# tottag.net
KiCad netlist of a schematic drawn in EAGLE
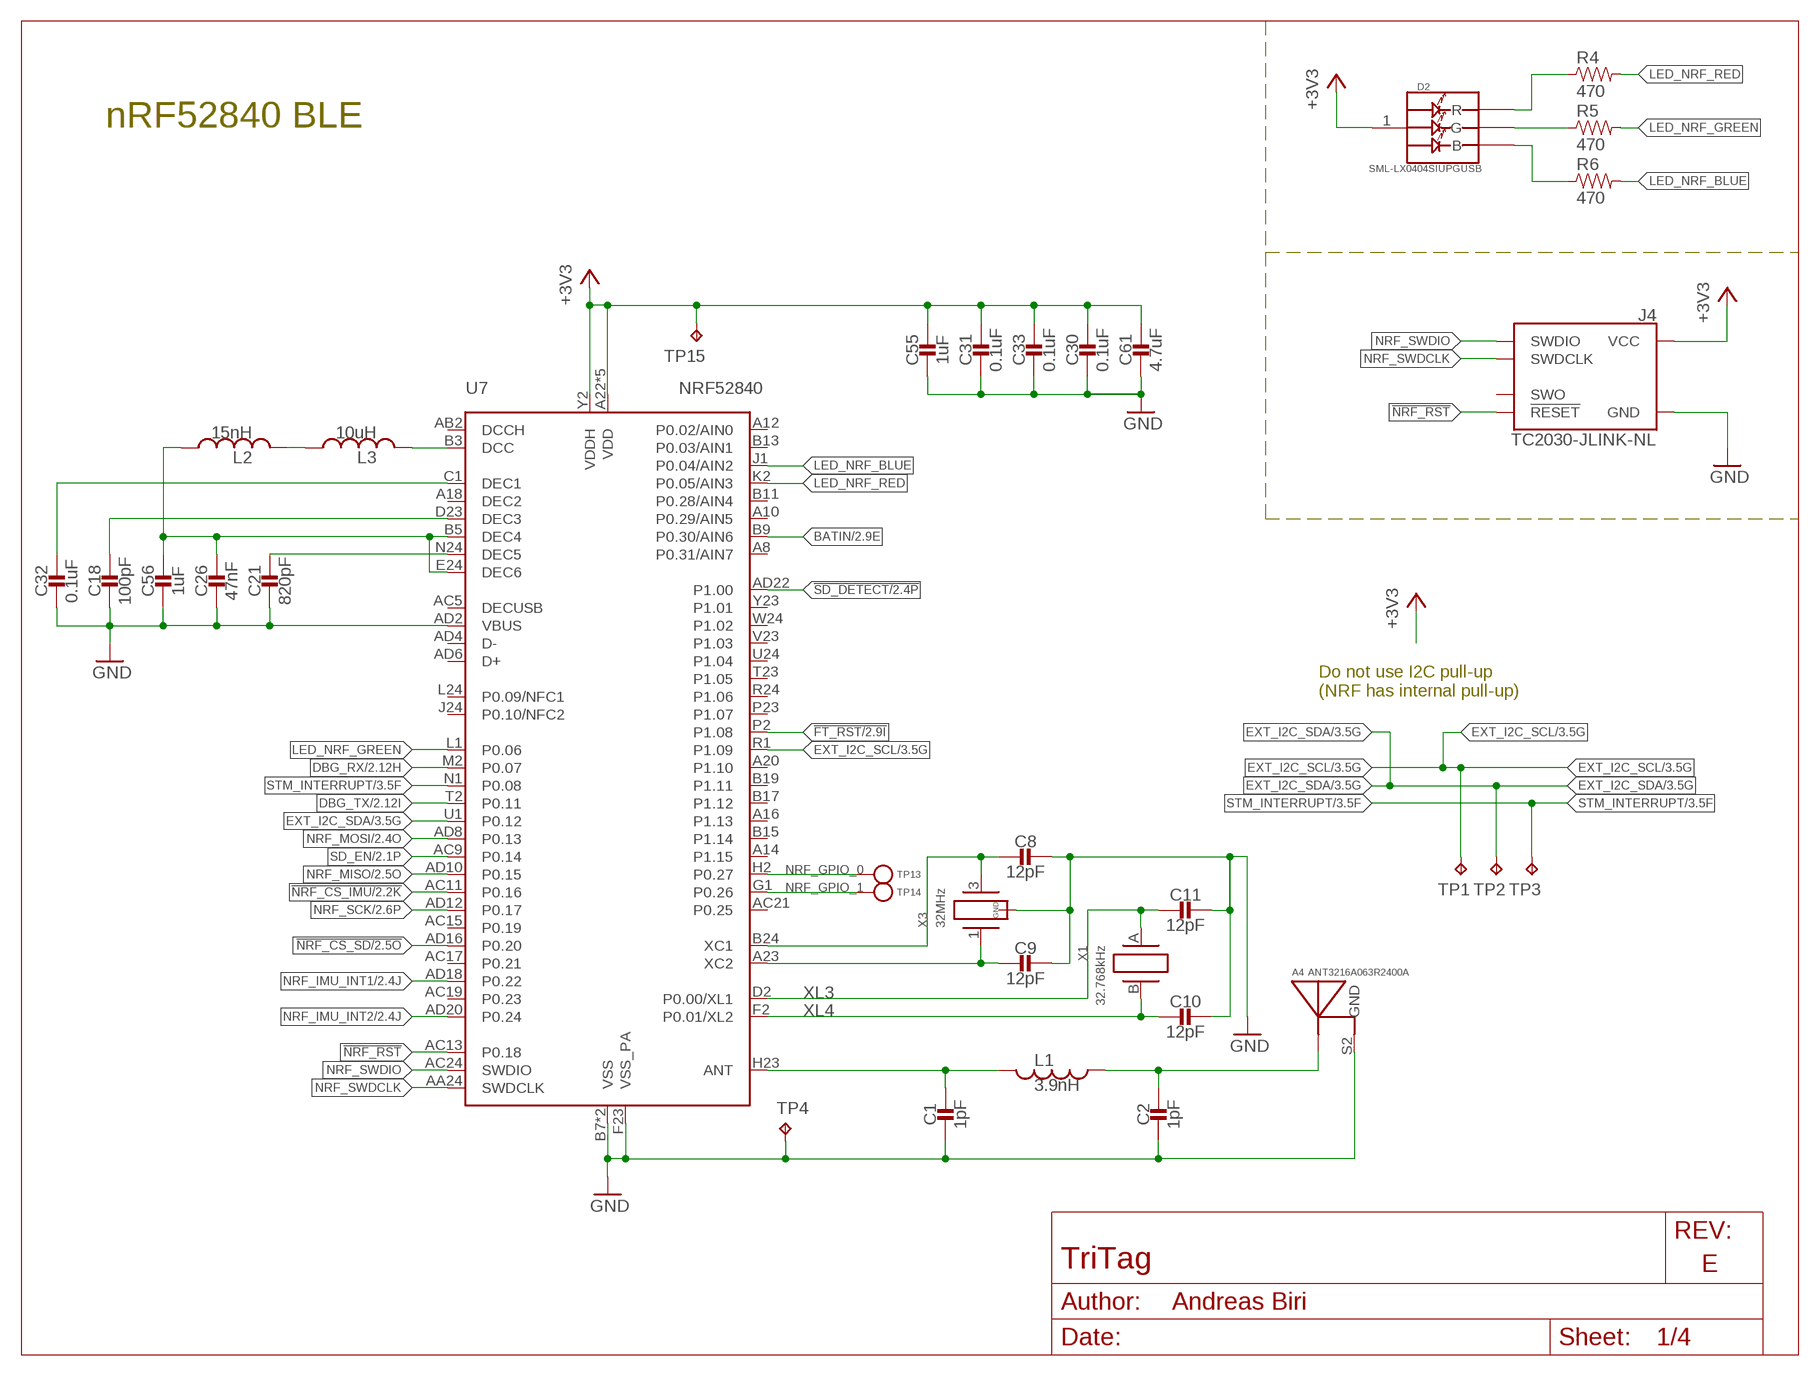
[diagram p0: schematic, sheet 1]
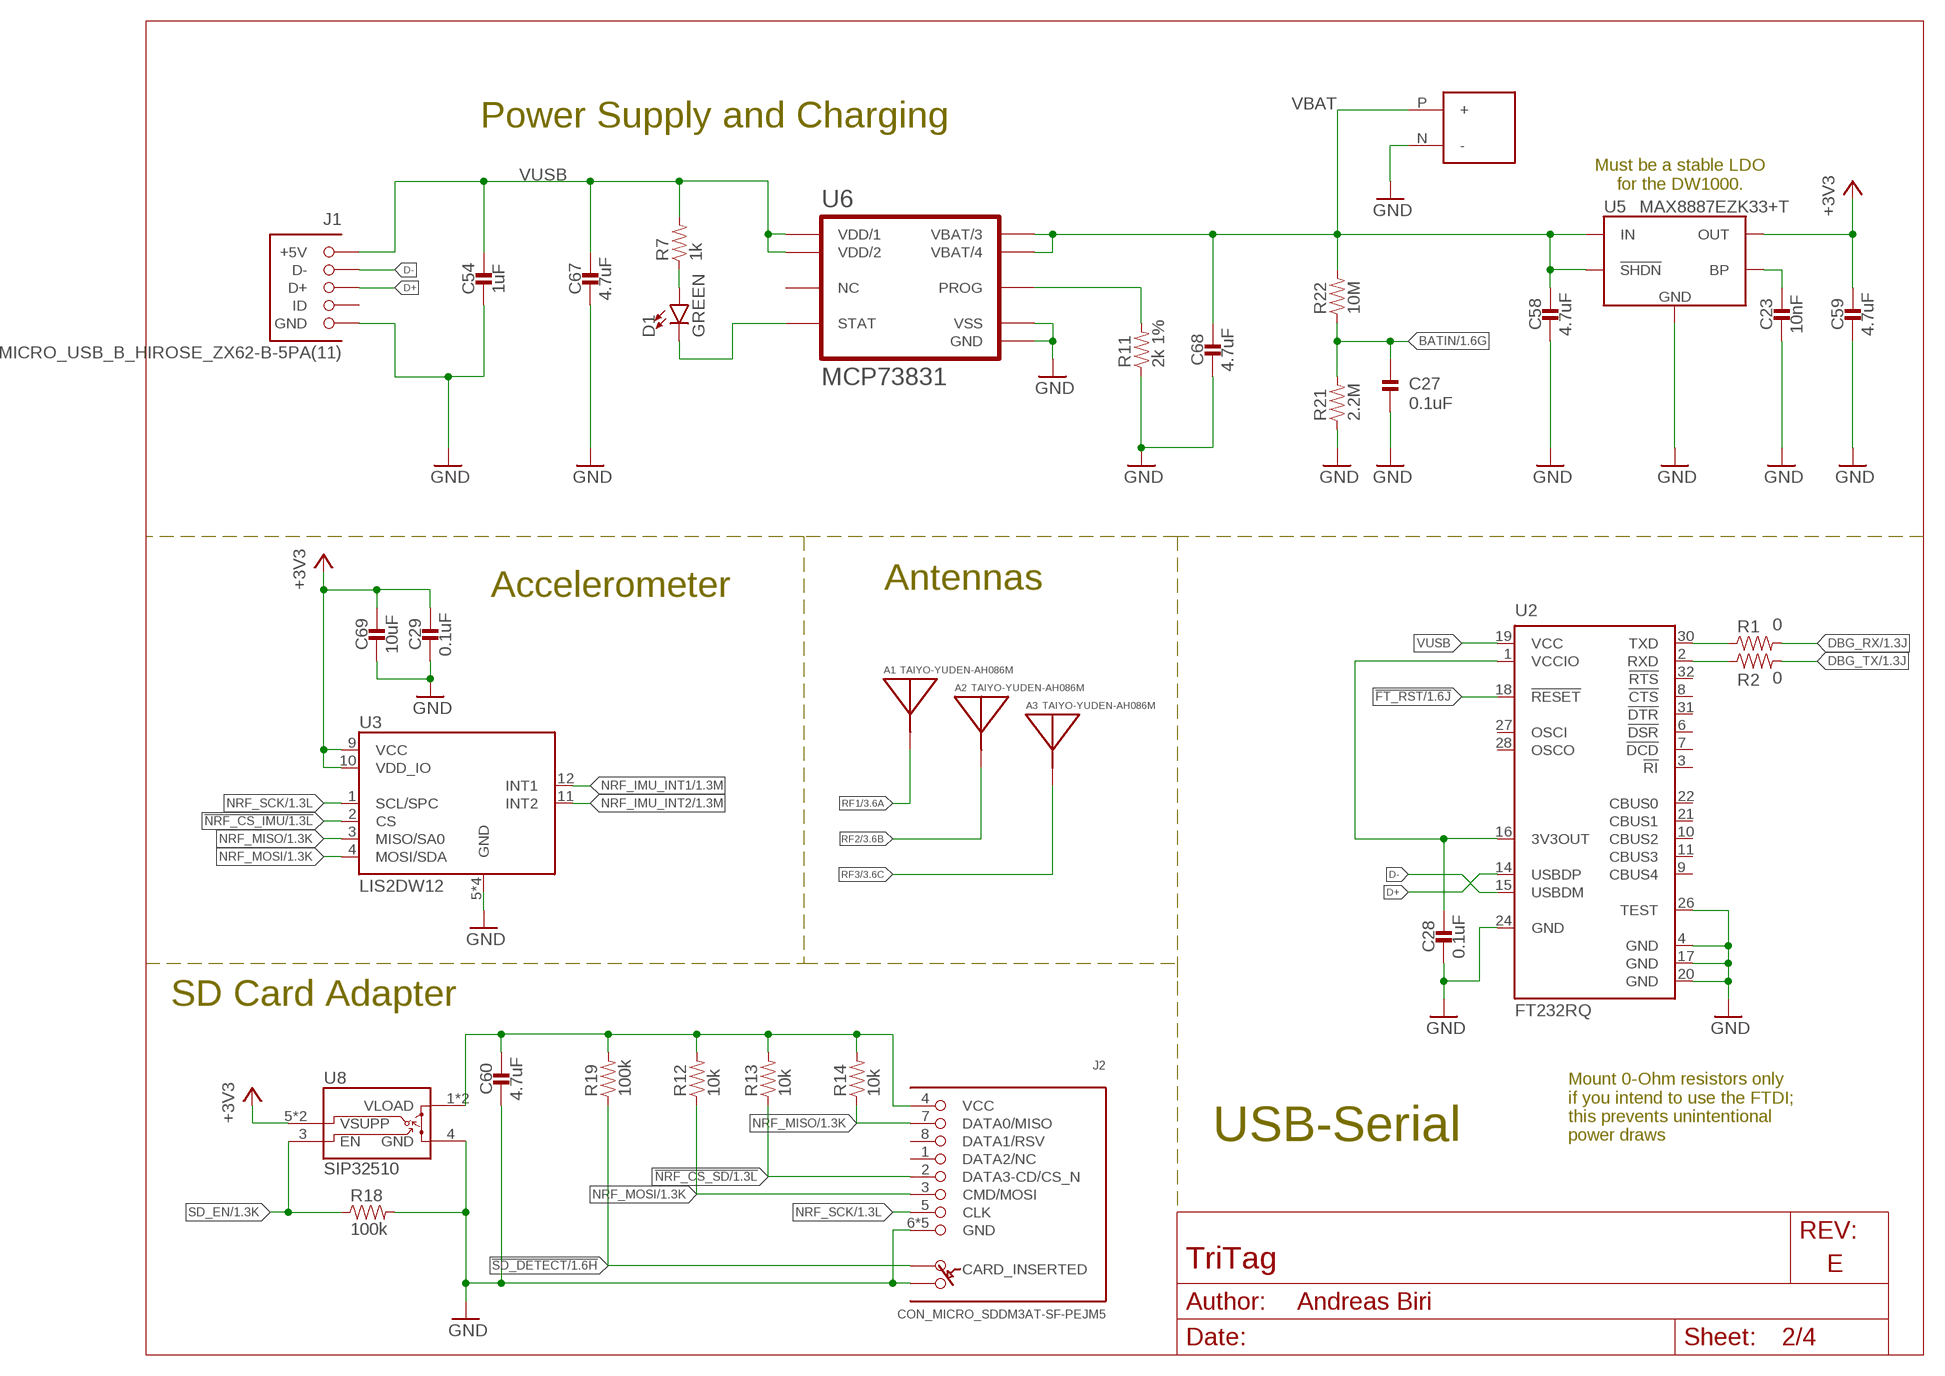
[diagram p1: schematic, sheet 2]
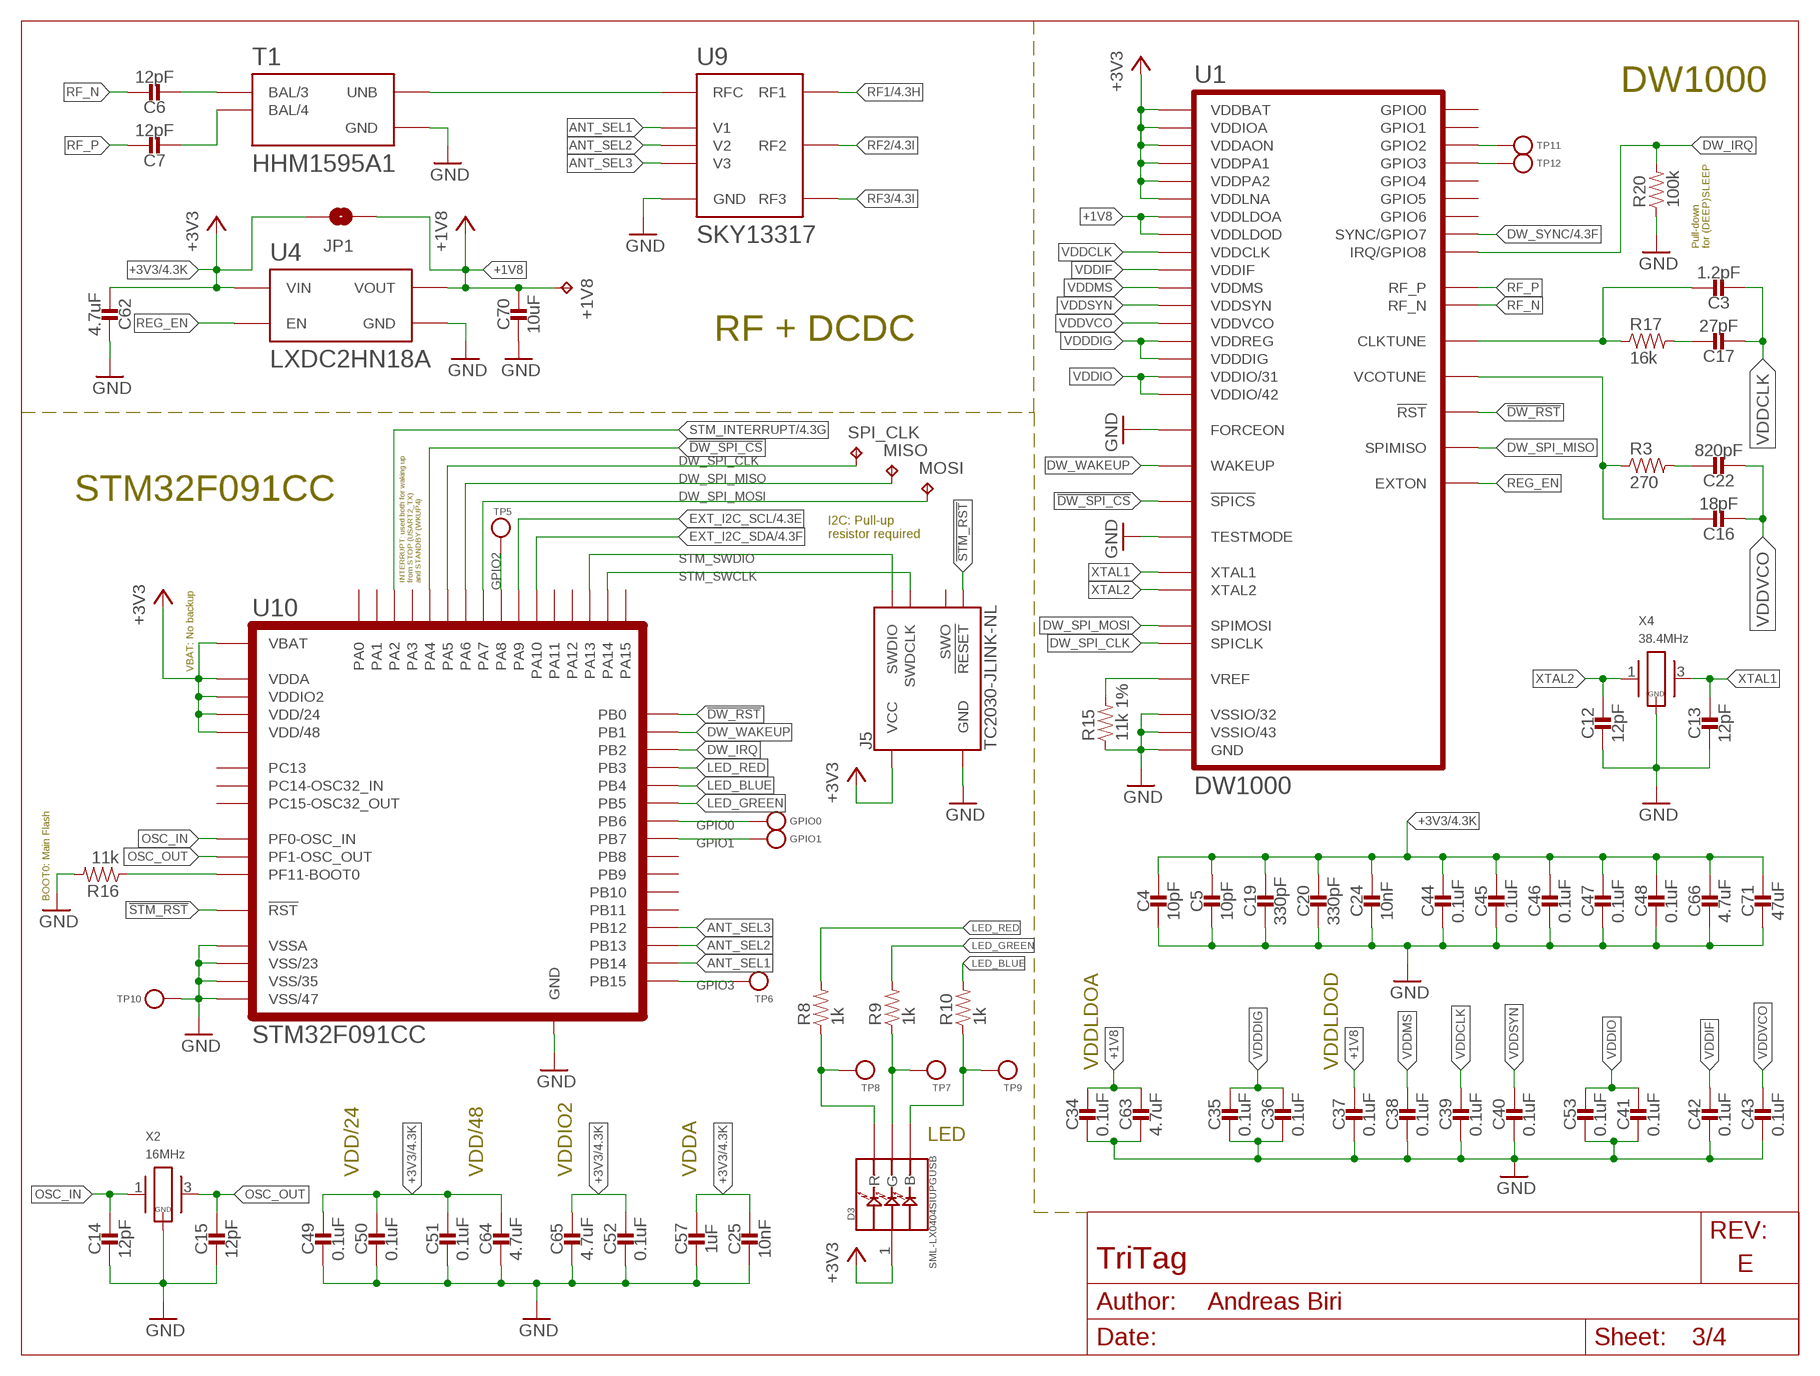
[diagram p2: schematic, sheet 3]
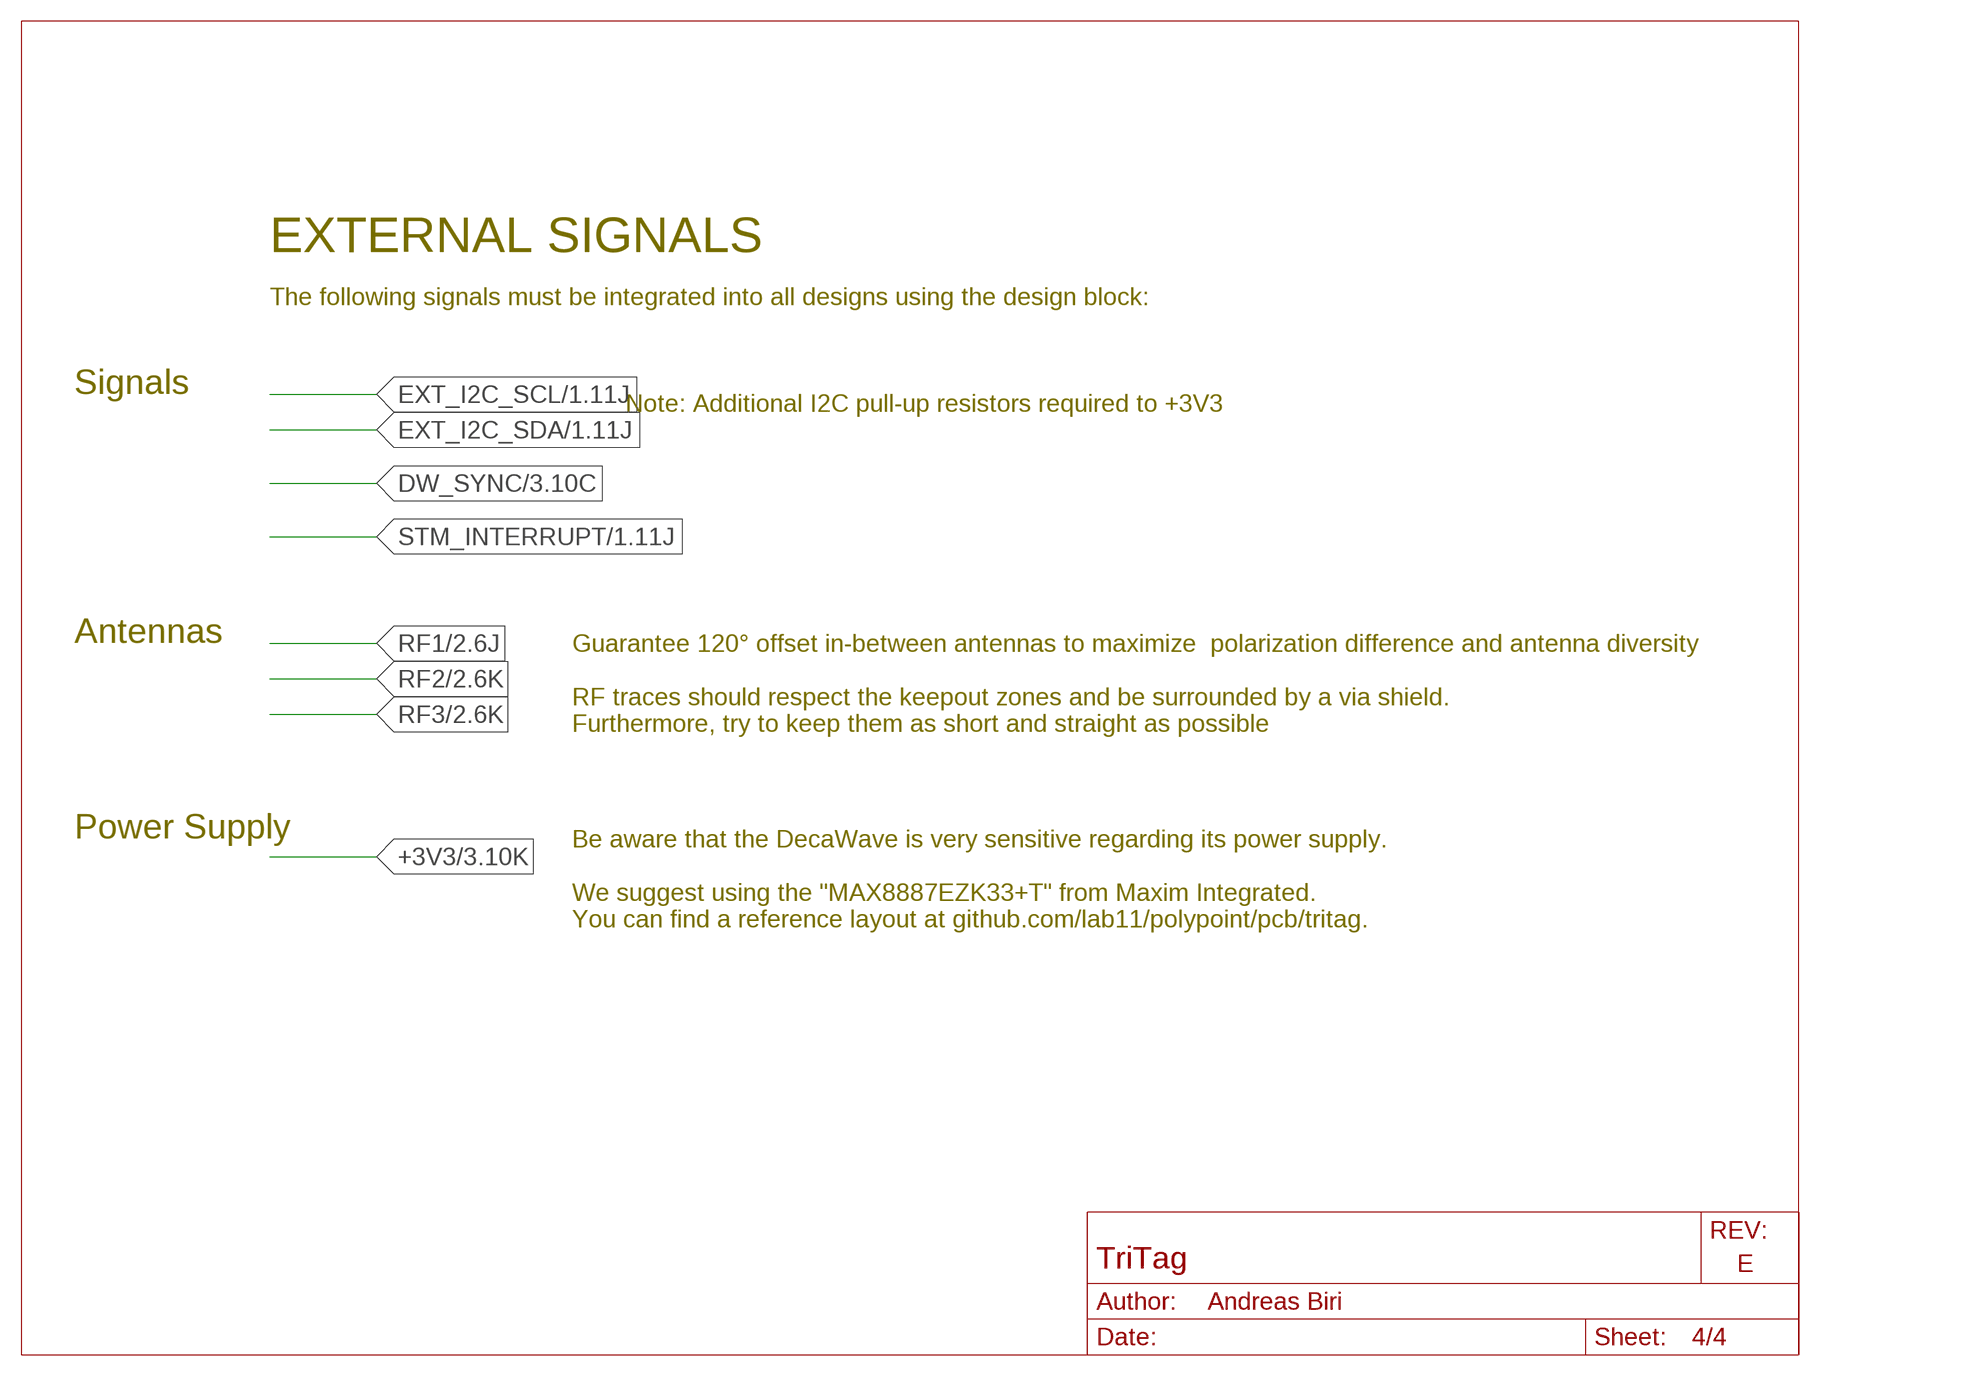
[diagram p3: schematic, sheet 4]

(export (version "E")
  (design (tool "Eeschema 10.0.6"))
  (components
    (comp (ref "A1")
      (value "TAIYO-YUDEN-AH086M")
      (footprint "eagle-import:TAIYO-YUDEN-AH086M")
      (libsource (lib "eagle-import") (part "TAIYO-YUDEN-AH086M"))
    )
    (comp (ref "A2")
      (value "TAIYO-YUDEN-AH086M")
      (footprint "eagle-import:TAIYO-YUDEN-AH086M")
      (libsource (lib "eagle-import") (part "TAIYO-YUDEN-AH086M"))
    )
    (comp (ref "A3")
      (value "TAIYO-YUDEN-AH086M")
      (footprint "eagle-import:TAIYO-YUDEN-AH086M")
      (libsource (lib "eagle-import") (part "TAIYO-YUDEN-AH086M"))
    )
    (comp (ref "C23")
      (value "10nF")
      (footprint "eagle-import:0402_CAP")
      (libsource (lib "eagle-import") (part "CAPACITOR0402_CAP"))
    )
    (comp (ref "C27")
      (value "0.1uF")
      (footprint "eagle-import:0402_CAP")
      (libsource (lib "eagle-import") (part "CAPACITOR0402_CAP"))
    )
    (comp (ref "C28")
      (value "0.1uF")
      (footprint "eagle-import:0402_CAP")
      (fields (field (name "MPN") "GRM155R71C104KA88J "))
      (libsource (lib "eagle-import") (part "CAPACITOR0402_CAP"))
    )
    (comp (ref "C29")
      (value "0.1uF")
      (footprint "eagle-import:0402_CAP")
      (fields (field (name "MPN") "GRM155R71C104KA88J "))
      (libsource (lib "eagle-import") (part "CAPACITOR0402_CAP"))
    )
    (comp (ref "C54")
      (value "1uF")
      (footprint "eagle-import:0402_CAP")
      (libsource (lib "eagle-import") (part "CAPACITOR0402_CAP"))
    )
    (comp (ref "C58")
      (value "4.7uF")
      (footprint "eagle-import:0402_CAP")
      (libsource (lib "eagle-import") (part "CAPACITOR0402_CAP"))
    )
    (comp (ref "C59")
      (value "4.7uF")
      (footprint "eagle-import:0402_CAP")
      (libsource (lib "eagle-import") (part "CAPACITOR0402_CAP"))
    )
    (comp (ref "C60")
      (value "4.7uF")
      (footprint "eagle-import:0402_CAP")
      (description "CAP CER 4.7UF 6.3V X5R 0402")
      (fields (field (name "MANUFACTURER") "TDK") (field (name "MPN") "C1005X5R0J475K050BC"))
      (libsource (lib "eagle-import") (part "CAPACITOR0402_CAP"))
    )
    (comp (ref "C67")
      (value "4.7uF")
      (footprint "eagle-import:0402_CAP")
      (libsource (lib "eagle-import") (part "CAPACITOR0402_CAP"))
    )
    (comp (ref "C68")
      (value "4.7uF")
      (footprint "eagle-import:0402_CAP")
      (libsource (lib "eagle-import") (part "CAPACITOR0402_CAP"))
    )
    (comp (ref "C69")
      (value "10uF")
      (footprint "eagle-import:0603_CAP")
      (fields (field (name "MPN") "GRM188R60J106ME47D "))
      (libsource (lib "eagle-import") (part "CAPACITOR0603_CAP"))
    )
    (comp (ref "D1")
      (value "GREEN")
      (footprint "eagle-import:LED-0603")
      (libsource (lib "eagle-import") (part "LED0603"))
    )
    (comp (ref "J1")
      (value "MICRO_USB_B_HIROSE_ZX62-B-5PA(11)")
      (footprint "eagle-import:USB_MICRO_B-HIROSE-ZX62-B-5PA(11)")
      (libsource (lib "eagle-import") (part "MICRO_USB_B_HIROSE_ZX62-B-5PA(11)"))
    )
    (comp (ref "J2")
      (value "CON_MICRO_SDDM3AT-SF-PEJM5")
      (footprint "eagle-import:DM3AT-SF-PEJM5")
      (libsource (lib "eagle-import") (part "CON_MICRO_SDDM3AT-SF-PEJM5"))
    )
    (comp (ref "J3")
      (value "BAT_HOLE")
      (footprint "eagle-import:BATTERY_HOLE")
      (libsource (lib "eagle-import") (part "BAT_HOLE"))
    )
    (comp (ref "R1")
      (value "0")
      (footprint "eagle-import:0402_RES")
      (libsource (lib "eagle-import") (part "RESISTOR0402_RES"))
    )
    (comp (ref "R2")
      (value "0")
      (footprint "eagle-import:0402_RES")
      (libsource (lib "eagle-import") (part "RESISTOR0402_RES"))
    )
    (comp (ref "R7")
      (value "1k")
      (footprint "eagle-import:0402_RES")
      (libsource (lib "eagle-import") (part "RESISTOR0402_RES"))
    )
    (comp (ref "R11")
      (value "2k 1%")
      (footprint "eagle-import:0402_RES")
      (libsource (lib "eagle-import") (part "RESISTOR0402_RES"))
    )
    (comp (ref "R12")
      (value "10k")
      (footprint "eagle-import:0402_RES")
      (libsource (lib "eagle-import") (part "RESISTOR0402_RES"))
    )
    (comp (ref "R13")
      (value "10k")
      (footprint "eagle-import:0402_RES")
      (libsource (lib "eagle-import") (part "RESISTOR0402_RES"))
    )
    (comp (ref "R14")
      (value "10k")
      (footprint "eagle-import:0402_RES")
      (libsource (lib "eagle-import") (part "RESISTOR0402_RES"))
    )
    (comp (ref "R18")
      (value "100k")
      (footprint "eagle-import:0402_RES")
      (libsource (lib "eagle-import") (part "RESISTOR0402_RES"))
    )
    (comp (ref "R19")
      (value "100k")
      (footprint "eagle-import:0402_RES")
      (libsource (lib "eagle-import") (part "RESISTOR0402_RES"))
    )
    (comp (ref "R21")
      (value "2.2M")
      (footprint "eagle-import:0402_RES")
      (libsource (lib "eagle-import") (part "RESISTOR0402_RES"))
    )
    (comp (ref "R22")
      (value "10M")
      (footprint "eagle-import:0402_RES")
      (libsource (lib "eagle-import") (part "RESISTOR0402_RES"))
    )
    (comp (ref "U2")
      (value "FT232RQ")
      (footprint "eagle-import:QFN32")
      (libsource (lib "eagle-import") (part "FT232RQ"))
    )
    (comp (ref "U3")
      (value "LIS2DW12")
      (footprint "eagle-import:LGA-12")
      (fields (field (name "MANUFACTURER") "STMicroelectronics") (field (name "MPN") "LIS2DW12TR"))
      (libsource (lib "eagle-import") (part "LIS2DW12"))
    )
    (comp (ref "U5")
      (value "MAX8887EZK33+T")
      (footprint "eagle-import:SOT-23-5")
      (libsource (lib "eagle-import") (part "MAX8887EZK33+T"))
    )
    (comp (ref "U6")
      (value "MCP73831")
      (footprint "eagle-import:DFN-8-MCP")
      (fields (field (name "MANUFACTURER") "Microchip Technology") (field (name "MPN") "MCP73831T-2ACI/MC"))
      (libsource (lib "eagle-import") (part "MCP73831"))
    )
    (comp (ref "U8")
      (value "SIP32510")
      (footprint "eagle-import:TSOT23-6")
      (fields (field (name "MANUFACTURER") "Vishay") (field (name "MPN") "SIP32510DT-T1-GE3"))
      (libsource (lib "eagle-import") (part "SIP32510"))
    )
    (comp (ref "+1V8")
      (value "TPTP06SQ")
      (footprint "eagle-import:TP06SQ")
      (libsource (lib "eagle-import") (part "TPTP06SQ"))
    )
    (comp (ref "C3")
      (value "1.2pF")
      (footprint "eagle-import:0402_CAP")
      (libsource (lib "eagle-import") (part "CAPACITOR0402_CAP"))
    )
    (comp (ref "C4")
      (value "10pF")
      (footprint "eagle-import:0402_CAP")
      (libsource (lib "eagle-import") (part "CAPACITOR0402_CAP"))
    )
    (comp (ref "C5")
      (value "10pF")
      (footprint "eagle-import:0402_CAP")
      (libsource (lib "eagle-import") (part "CAPACITOR0402_CAP"))
    )
    (comp (ref "C6")
      (value "12pF")
      (footprint "eagle-import:0201_CAP")
      (libsource (lib "eagle-import") (part "CAPACITOR0201_CAP"))
    )
    (comp (ref "C7")
      (value "12pF")
      (footprint "eagle-import:0201_CAP")
      (libsource (lib "eagle-import") (part "CAPACITOR0201_CAP"))
    )
    (comp (ref "C12")
      (value "12pF")
      (footprint "eagle-import:0402_CAP")
      (libsource (lib "eagle-import") (part "CAPACITOR0402_CAP"))
    )
    (comp (ref "C13")
      (value "12pF")
      (footprint "eagle-import:0402_CAP")
      (libsource (lib "eagle-import") (part "CAPACITOR0402_CAP"))
    )
    (comp (ref "C14")
      (value "12pF")
      (footprint "eagle-import:0402_CAP")
      (libsource (lib "eagle-import") (part "CAPACITOR0402_CAP"))
    )
    (comp (ref "C15")
      (value "12pF")
      (footprint "eagle-import:0402_CAP")
      (libsource (lib "eagle-import") (part "CAPACITOR0402_CAP"))
    )
    (comp (ref "C16")
      (value "18pF")
      (footprint "eagle-import:0402_CAP")
      (libsource (lib "eagle-import") (part "CAPACITOR0402_CAP"))
    )
    (comp (ref "C17")
      (value "27pF")
      (footprint "eagle-import:0402_CAP")
      (libsource (lib "eagle-import") (part "CAPACITOR0402_CAP"))
    )
    (comp (ref "C19")
      (value "330pF")
      (footprint "eagle-import:0402_CAP")
      (libsource (lib "eagle-import") (part "CAPACITOR0402_CAP"))
    )
    (comp (ref "C20")
      (value "330pF")
      (footprint "eagle-import:0402_CAP")
      (libsource (lib "eagle-import") (part "CAPACITOR0402_CAP"))
    )
    (comp (ref "C22")
      (value "820pF")
      (footprint "eagle-import:0402_CAP")
      (libsource (lib "eagle-import") (part "CAPACITOR0402_CAP"))
    )
    (comp (ref "C24")
      (value "10nF")
      (footprint "eagle-import:0402_CAP")
      (libsource (lib "eagle-import") (part "CAPACITOR0402_CAP"))
    )
    (comp (ref "C25")
      (value "10nF")
      (footprint "eagle-import:0402_CAP")
      (libsource (lib "eagle-import") (part "CAPACITOR0402_CAP"))
    )
    (comp (ref "C34")
      (value "0.1uF")
      (footprint "eagle-import:0402_CAP")
      (libsource (lib "eagle-import") (part "CAPACITOR0402_CAP"))
    )
    (comp (ref "C35")
      (value "0.1uF")
      (footprint "eagle-import:0402_CAP")
      (libsource (lib "eagle-import") (part "CAPACITOR0402_CAP"))
    )
    (comp (ref "C36")
      (value "0.1uF")
      (footprint "eagle-import:0402_CAP")
      (libsource (lib "eagle-import") (part "CAPACITOR0402_CAP"))
    )
    (comp (ref "C37")
      (value "0.1uF")
      (footprint "eagle-import:0402_CAP")
      (libsource (lib "eagle-import") (part "CAPACITOR0402_CAP"))
    )
    (comp (ref "C38")
      (value "0.1uF")
      (footprint "eagle-import:0402_CAP")
      (libsource (lib "eagle-import") (part "CAPACITOR0402_CAP"))
    )
    (comp (ref "C39")
      (value "0.1uF")
      (footprint "eagle-import:0402_CAP")
      (libsource (lib "eagle-import") (part "CAPACITOR0402_CAP"))
    )
    (comp (ref "C40")
      (value "0.1uF")
      (footprint "eagle-import:0402_CAP")
      (libsource (lib "eagle-import") (part "CAPACITOR0402_CAP"))
    )
    (comp (ref "C41")
      (value "0.1uF")
      (footprint "eagle-import:0402_CAP")
      (libsource (lib "eagle-import") (part "CAPACITOR0402_CAP"))
    )
    (comp (ref "C42")
      (value "0.1uF")
      (footprint "eagle-import:0402_CAP")
      (libsource (lib "eagle-import") (part "CAPACITOR0402_CAP"))
    )
    (comp (ref "C43")
      (value "0.1uF")
      (footprint "eagle-import:0402_CAP")
      (libsource (lib "eagle-import") (part "CAPACITOR0402_CAP"))
    )
    (comp (ref "C44")
      (value "0.1uF")
      (footprint "eagle-import:0402_CAP")
      (libsource (lib "eagle-import") (part "CAPACITOR0402_CAP"))
    )
    (comp (ref "C45")
      (value "0.1uF")
      (footprint "eagle-import:0402_CAP")
      (libsource (lib "eagle-import") (part "CAPACITOR0402_CAP"))
    )
    (comp (ref "C46")
      (value "0.1uF")
      (footprint "eagle-import:0402_CAP")
      (libsource (lib "eagle-import") (part "CAPACITOR0402_CAP"))
    )
    (comp (ref "C47")
      (value "0.1uF")
      (footprint "eagle-import:0402_CAP")
      (libsource (lib "eagle-import") (part "CAPACITOR0402_CAP"))
    )
    (comp (ref "C48")
      (value "0.1uF")
      (footprint "eagle-import:0402_CAP")
      (libsource (lib "eagle-import") (part "CAPACITOR0402_CAP"))
    )
    (comp (ref "C49")
      (value "0.1uF")
      (footprint "eagle-import:0402_CAP")
      (libsource (lib "eagle-import") (part "CAPACITOR0402_CAP"))
    )
    (comp (ref "C50")
      (value "0.1uF")
      (footprint "eagle-import:0402_CAP")
      (libsource (lib "eagle-import") (part "CAPACITOR0402_CAP"))
    )
    (comp (ref "C51")
      (value "0.1uF")
      (footprint "eagle-import:0402_CAP")
      (libsource (lib "eagle-import") (part "CAPACITOR0402_CAP"))
    )
    (comp (ref "C52")
      (value "0.1uF")
      (footprint "eagle-import:0402_CAP")
      (libsource (lib "eagle-import") (part "CAPACITOR0402_CAP"))
    )
    (comp (ref "C53")
      (value "0.1uF")
      (footprint "eagle-import:0402_CAP")
      (libsource (lib "eagle-import") (part "CAPACITOR0402_CAP"))
    )
    (comp (ref "C57")
      (value "1uF")
      (footprint "eagle-import:0402_CAP")
      (libsource (lib "eagle-import") (part "CAPACITOR0402_CAP"))
    )
    (comp (ref "C62")
      (value "4.7uF")
      (footprint "eagle-import:0402_CAP")
      (libsource (lib "eagle-import") (part "CAPACITOR0402_CAP"))
    )
    (comp (ref "C63")
      (value "4.7uF")
      (footprint "eagle-import:0402_CAP")
      (libsource (lib "eagle-import") (part "CAPACITOR0402_CAP"))
    )
    (comp (ref "C64")
      (value "4.7uF")
      (footprint "eagle-import:0402_CAP")
      (libsource (lib "eagle-import") (part "CAPACITOR0402_CAP"))
    )
    (comp (ref "C65")
      (value "4.7uF")
      (footprint "eagle-import:0402_CAP")
      (libsource (lib "eagle-import") (part "CAPACITOR0402_CAP"))
    )
    (comp (ref "C66")
      (value "4.7uF")
      (footprint "eagle-import:0402_CAP")
      (libsource (lib "eagle-import") (part "CAPACITOR0402_CAP"))
    )
    (comp (ref "C70")
      (value "10uF")
      (footprint "eagle-import:0603_CAP")
      (libsource (lib "eagle-import") (part "CAPACITOR0603_CAP"))
    )
    (comp (ref "C71")
      (value "47uF")
      (footprint "eagle-import:0603_CAP")
      (libsource (lib "eagle-import") (part "CAPACITOR0603_CAP"))
    )
    (comp (ref "D3")
      (value "SML-LX0404SIUPGUSB")
      (footprint "eagle-import:1MM_SQ_4PAD")
      (fields (field (name "MANUFACTURER") "Lumex Opto"))
      (libsource (lib "eagle-import") (part "SML-LX0404SIUPGUSB"))
    )
    (comp (ref "GPIO0")
      (value "TEST-POINT")
      (footprint "eagle-import:PAD.03X.03")
      (libsource (lib "eagle-import") (part "TEST-POINT"))
    )
    (comp (ref "GPIO1")
      (value "TEST-POINT")
      (footprint "eagle-import:PAD.03X.03")
      (libsource (lib "eagle-import") (part "TEST-POINT"))
    )
    (comp (ref "J5")
      (value "TC2030-JLINK-NL")
      (footprint "eagle-import:TC2030-IDC-NL")
      (libsource (lib "eagle-import") (part "TC2030-JLINK-NL"))
    )
    (comp (ref "JP1")
      (value "JUMPER-SMT_2_NO_NO-SILK")
      (footprint "eagle-import:SMT-JUMPER_2_NO_NO-SILK")
      (libsource (lib "eagle-import") (part "JUMPER-SMT_2_NO_NO-SILK"))
    )
    (comp (ref "MISO")
      (value "TPTP06SQ")
      (footprint "eagle-import:TP06SQ")
      (libsource (lib "eagle-import") (part "TPTP06SQ"))
    )
    (comp (ref "MOSI")
      (value "TPTP06SQ")
      (footprint "eagle-import:TP06SQ")
      (libsource (lib "eagle-import") (part "TPTP06SQ"))
    )
    (comp (ref "R3")
      (value "270")
      (footprint "eagle-import:0402_RES")
      (libsource (lib "eagle-import") (part "RESISTOR0402_RES"))
    )
    (comp (ref "R8")
      (value "1k")
      (footprint "eagle-import:0402_RES")
      (libsource (lib "eagle-import") (part "RESISTOR0402_RES"))
    )
    (comp (ref "R9")
      (value "1k")
      (footprint "eagle-import:0402_RES")
      (libsource (lib "eagle-import") (part "RESISTOR0402_RES"))
    )
    (comp (ref "R10")
      (value "1k")
      (footprint "eagle-import:0402_RES")
      (libsource (lib "eagle-import") (part "RESISTOR0402_RES"))
    )
    (comp (ref "R15")
      (value "11k 1%")
      (footprint "eagle-import:0402_RES")
      (libsource (lib "eagle-import") (part "RESISTOR0402_RES"))
    )
    (comp (ref "R16")
      (value "11k")
      (footprint "eagle-import:0402_RES")
      (libsource (lib "eagle-import") (part "RESISTOR0402_RES"))
    )
    (comp (ref "R17")
      (value "16k")
      (footprint "eagle-import:0402_RES")
      (libsource (lib "eagle-import") (part "RESISTOR0402_RES"))
    )
    (comp (ref "R20")
      (value "100k")
      (footprint "eagle-import:0402_RES")
      (libsource (lib "eagle-import") (part "RESISTOR0402_RES"))
    )
    (comp (ref "SPI_CLK")
      (value "TPTP06SQ")
      (footprint "eagle-import:TP06SQ")
      (libsource (lib "eagle-import") (part "TPTP06SQ"))
    )
    (comp (ref "T1")
      (value "HHM1595A1")
      (footprint "eagle-import:EIA-0805")
      (fields (field (name "MANUFACTURER") "TDK Corporation"))
      (libsource (lib "eagle-import") (part "HHM1595A1"))
    )
    (comp (ref "TP5")
      (value "TEST-POINT")
      (footprint "eagle-import:PAD.03X.03")
      (libsource (lib "eagle-import") (part "TEST-POINT"))
    )
    (comp (ref "TP6")
      (value "TEST-POINT")
      (footprint "eagle-import:PAD.03X.03")
      (libsource (lib "eagle-import") (part "TEST-POINT"))
    )
    (comp (ref "TP7")
      (value "TEST-POINT")
      (footprint "eagle-import:PAD.03X.03")
      (libsource (lib "eagle-import") (part "TEST-POINT"))
    )
    (comp (ref "TP8")
      (value "TEST-POINT")
      (footprint "eagle-import:PAD.03X.03")
      (libsource (lib "eagle-import") (part "TEST-POINT"))
    )
    (comp (ref "TP9")
      (value "TEST-POINT")
      (footprint "eagle-import:PAD.03X.03")
      (libsource (lib "eagle-import") (part "TEST-POINT"))
    )
    (comp (ref "TP10")
      (value "TEST-POINT")
      (footprint "eagle-import:PAD.03X.03")
      (libsource (lib "eagle-import") (part "TEST-POINT"))
    )
    (comp (ref "TP11")
      (value "TEST-POINT")
      (footprint "eagle-import:PAD.03X.03")
      (libsource (lib "eagle-import") (part "TEST-POINT"))
    )
    (comp (ref "TP12")
      (value "TEST-POINT")
      (footprint "eagle-import:PAD.03X.03")
      (libsource (lib "eagle-import") (part "TEST-POINT"))
    )
    (comp (ref "U1")
      (value "DW1000")
      (footprint "eagle-import:QFN-48-DW1000")
      (fields (field (name "MANUFACTURER") "Decawave Limited") (field (name "MPN") "DW1000-I-TR13"))
      (libsource (lib "eagle-import") (part "DW1000"))
    )
    (comp (ref "U4")
      (value "LXDC2HN18A")
      (footprint "eagle-import:LXDC2HN")
      (fields
        (field (name "MANUFACTURER") "Murata Electronics North America")
        (field (name "MPN") "LXDC2HN18A-097")
      )
      (libsource (lib "eagle-import") (part "LXDC2HN18A"))
    )
    (comp (ref "U9")
      (value "SKY13317")
      (footprint "eagle-import:MLPQ-UT-8")
      (fields (field (name "MANUFACTURER") "Skyworks Solutions Inc.") (field (name "MPN") "SKY13317-373LF"))
      (libsource (lib "eagle-import") (part "SKY13317"))
    )
    (comp (ref "U10")
      (value "STM32F091CC")
      (footprint "eagle-import:UFQFPN-48")
      (fields (field (name "MANUFACTURER") "STMicroelectronics") (field (name "MPN") "STM32F091CCU6"))
      (libsource (lib "eagle-import") (part "STM32F091CC"))
    )
    (comp (ref "X2")
      (value "16MHz")
      (footprint "eagle-import:FA-20H")
      (description "16MHz ±10ppm Crystal 8pF 80 Ohms 4-SMD, No Lead")
      (fields (field (name "MANUFACTURER") "EPSON"))
      (libsource (lib "eagle-import") (part "FA-20H"))
    )
    (comp (ref "X4")
      (value "38.4MHz")
      (footprint "eagle-import:FA-20H")
      (description "38.4MHz ±10ppm Crystal 8.5pF 40 Ohms 4-SMD, No Lead")
      (fields (field (name "MANUFACTURER") "EPSON"))
      (libsource (lib "eagle-import") (part "FA-20H"))
    )
    (comp (ref "A4")
      (value "ANT3216A063R2400A")
      (footprint "eagle-import:ANT3216A063R2400A")
      (fields (field (name "MANUFACTURER") "YAGEO"))
      (libsource (lib "eagle-import") (part "ANT3216A063R2400A"))
    )
    (comp (ref "C1")
      (value "1pF")
      (footprint "eagle-import:0402_CAP")
      (fields (field (name "MPN") "GJM1555C1H1R0CB01D "))
      (libsource (lib "eagle-import") (part "CAPACITOR0402_CAP"))
    )
    (comp (ref "C2")
      (value "1pF")
      (footprint "eagle-import:0402_CAP")
      (fields (field (name "MPN") "GJM1555C1H1R0CB01D"))
      (libsource (lib "eagle-import") (part "CAPACITOR0402_CAP"))
    )
    (comp (ref "C8")
      (value "12pF")
      (footprint "eagle-import:0402_CAP")
      (fields (field (name "MPN") "GRM1555C1H120GA01D "))
      (libsource (lib "eagle-import") (part "CAPACITOR0402_CAP"))
    )
    (comp (ref "C9")
      (value "12pF")
      (footprint "eagle-import:0402_CAP")
      (fields (field (name "MPN") "GRM1555C1H120GA01D "))
      (libsource (lib "eagle-import") (part "CAPACITOR0402_CAP"))
    )
    (comp (ref "C10")
      (value "12pF")
      (footprint "eagle-import:0402_CAP")
      (fields (field (name "MPN") "GRM1555C1H120GA01D "))
      (libsource (lib "eagle-import") (part "CAPACITOR0402_CAP"))
    )
    (comp (ref "C11")
      (value "12pF")
      (footprint "eagle-import:0402_CAP")
      (fields (field (name "MPN") "GRM1555C1H120GA01D "))
      (libsource (lib "eagle-import") (part "CAPACITOR0402_CAP"))
    )
    (comp (ref "C18")
      (value "100pF")
      (footprint "eagle-import:0402_CAP")
      (fields (field (name "MPN") "GRM1555C1H101JA01D "))
      (libsource (lib "eagle-import") (part "CAPACITOR0402_CAP"))
    )
    (comp (ref "C21")
      (value "820pF")
      (footprint "eagle-import:0402_CAP")
      (fields (field (name "MPN") "CL05C821JB5NFNC"))
      (libsource (lib "eagle-import") (part "CAPACITOR0402_CAP"))
    )
    (comp (ref "C26")
      (value "47nF")
      (footprint "eagle-import:0402_CAP")
      (fields (field (name "MPN") "C1005X7R1C473K050BC "))
      (libsource (lib "eagle-import") (part "CAPACITOR0402_CAP"))
    )
    (comp (ref "C30")
      (value "0.1uF")
      (footprint "eagle-import:0402_CAP")
      (fields (field (name "MPN") "GRM155R71C104KA88J "))
      (libsource (lib "eagle-import") (part "CAPACITOR0402_CAP"))
    )
    (comp (ref "C31")
      (value "0.1uF")
      (footprint "eagle-import:0402_CAP")
      (libsource (lib "eagle-import") (part "CAPACITOR0402_CAP"))
    )
    (comp (ref "C32")
      (value "0.1uF")
      (footprint "eagle-import:0402_CAP")
      (fields (field (name "MPN") "GRM155R71C104KA88J "))
      (libsource (lib "eagle-import") (part "CAPACITOR0402_CAP"))
    )
    (comp (ref "C33")
      (value "0.1uF")
      (footprint "eagle-import:0402_CAP")
      (fields (field (name "MPN") "GRM155R71C104KA88J "))
      (libsource (lib "eagle-import") (part "CAPACITOR0402_CAP"))
    )
    (comp (ref "C55")
      (value "1uF")
      (footprint "eagle-import:0402_CAP")
      (libsource (lib "eagle-import") (part "CAPACITOR0402_CAP"))
    )
    (comp (ref "C56")
      (value "1uF")
      (footprint "eagle-import:0402_CAP")
      (fields (field (name "MPN") "GRM155R70G105KA12D "))
      (libsource (lib "eagle-import") (part "CAPACITOR0402_CAP"))
    )
    (comp (ref "C61")
      (value "4.7uF")
      (footprint "eagle-import:0402_CAP")
      (libsource (lib "eagle-import") (part "CAPACITOR0402_CAP"))
    )
    (comp (ref "D2")
      (value "SML-LX0404SIUPGUSB")
      (footprint "eagle-import:1MM_SQ_4PAD")
      (fields (field (name "MANUFACTURER") "Lumex Opto"))
      (libsource (lib "eagle-import") (part "SML-LX0404SIUPGUSB"))
    )
    (comp (ref "J4")
      (value "TC2030-JLINK-NL")
      (footprint "eagle-import:TC2030-IDC-NL")
      (libsource (lib "eagle-import") (part "TC2030-JLINK-NL"))
    )
    (comp (ref "L1")
      (value "3.9nH")
      (footprint "eagle-import:0402_CAP")
      (fields (field (name "MPN") "AISC-0402-3N9G-T "))
      (libsource (lib "eagle-import") (part "INDUCTOR0402"))
    )
    (comp (ref "L2")
      (value "15nH")
      (footprint "eagle-import:0402_CAP")
      (fields (field (name "MPN") "HK100515NJ-T "))
      (libsource (lib "eagle-import") (part "INDUCTOR0402"))
    )
    (comp (ref "L3")
      (value "10uH")
      (footprint "eagle-import:0603_CAP")
      (fields (field (name "MPN") "LQM18FN100M00D "))
      (libsource (lib "eagle-import") (part "INDUCTOR0603"))
    )
    (comp (ref "R4")
      (value "470")
      (footprint "eagle-import:0402_RES")
      (libsource (lib "eagle-import") (part "RESISTOR0402_RES"))
    )
    (comp (ref "R5")
      (value "470")
      (footprint "eagle-import:0402_RES")
      (libsource (lib "eagle-import") (part "RESISTOR0402_RES"))
    )
    (comp (ref "R6")
      (value "470")
      (footprint "eagle-import:0402_RES")
      (libsource (lib "eagle-import") (part "RESISTOR0402_RES"))
    )
    (comp (ref "TP1")
      (value "TPTP06SQ")
      (footprint "eagle-import:TP06SQ")
      (libsource (lib "eagle-import") (part "TPTP06SQ"))
    )
    (comp (ref "TP2")
      (value "TPTP06SQ")
      (footprint "eagle-import:TP06SQ")
      (libsource (lib "eagle-import") (part "TPTP06SQ"))
    )
    (comp (ref "TP3")
      (value "TPTP06SQ")
      (footprint "eagle-import:TP06SQ")
      (libsource (lib "eagle-import") (part "TPTP06SQ"))
    )
    (comp (ref "TP4")
      (value "TPTP06SQ")
      (footprint "eagle-import:TP06SQ")
      (libsource (lib "eagle-import") (part "TPTP06SQ"))
    )
    (comp (ref "TP13")
      (value "TEST-POINT")
      (footprint "eagle-import:PAD.03X.03")
      (libsource (lib "eagle-import") (part "TEST-POINT"))
    )
    (comp (ref "TP14")
      (value "TEST-POINT")
      (footprint "eagle-import:PAD.03X.03")
      (libsource (lib "eagle-import") (part "TEST-POINT"))
    )
    (comp (ref "TP15")
      (value "TPTP06SQ")
      (footprint "eagle-import:TP06SQ")
      (libsource (lib "eagle-import") (part "TPTP06SQ"))
    )
    (comp (ref "U7")
      (value "NRF52840")
      (footprint "eagle-import:AQFN73")
      (fields (field (name "MANUFACTURER") "NORIDIC SEMICONDUCTOR"))
      (libsource (lib "eagle-import") (part "NRF52840"))
    )
    (comp (ref "X1")
      (value "32.768kHz")
      (footprint "eagle-import:ABS05")
      (fields (field (name "MANUFACTURER") "Abracon") (field (name "MPN") "ABS05-32.768KHZ-9-T"))
      (libsource (lib "eagle-import") (part "ABS05-32.768KHZ-9-T"))
    )
    (comp (ref "X3")
      (value "32MHz")
      (footprint "eagle-import:TXC-7V")
      (fields (field (name "MANUFACTURER") "TXC CORPORATION") (field (name "MPN") "7M-32.000MAHV-T"))
      (libsource (lib "eagle-import") (part "7V-32.000MAHV-T"))
    )
  )
  (nets
    (net (code "1") (name "+1V8") (class "Default")
      (node (ref "+1V8") (pin "TP") (pinfunction "TP_TP") (pintype "input"))
      (node (ref "C34") (pin "1") (pinfunction "1_1") (pintype "bidirectional"))
      (node (ref "C37") (pin "1") (pinfunction "1_1") (pintype "bidirectional"))
      (node (ref "C63") (pin "1") (pinfunction "1_1") (pintype "bidirectional"))
      (node (ref "C70") (pin "1") (pinfunction "1_1") (pintype "bidirectional"))
      (node (ref "JP1") (pin "2") (pinfunction "2_2") (pintype "passive"))
      (node (ref "U1") (pin "26") (pinfunction "VDDLDOD_26") (pintype "power_in"))
      (node (ref "U1") (pin "48") (pinfunction "VDDLDOA_48") (pintype "power_in"))
      (node (ref "U4") (pin "3") (pinfunction "VOUT_3") (pintype "power_in"))
    )
    (net (code "2") (name "+3V3") (class "Default")
      (node (ref "C19") (pin "1") (pinfunction "1_1") (pintype "bidirectional"))
      (node (ref "C20") (pin "1") (pinfunction "1_1") (pintype "bidirectional"))
      (node (ref "C24") (pin "1") (pinfunction "1_1") (pintype "bidirectional"))
      (node (ref "C25") (pin "1") (pinfunction "1_1") (pintype "bidirectional"))
      (node (ref "C29") (pin "1") (pinfunction "1_1") (pintype "bidirectional"))
      (node (ref "C30") (pin "1") (pinfunction "1_1") (pintype "bidirectional"))
      (node (ref "C31") (pin "1") (pinfunction "1_1") (pintype "bidirectional"))
      (node (ref "C33") (pin "1") (pinfunction "1_1") (pintype "bidirectional"))
      (node (ref "C4") (pin "1") (pinfunction "1_1") (pintype "bidirectional"))
      (node (ref "C44") (pin "1") (pinfunction "1_1") (pintype "bidirectional"))
      (node (ref "C45") (pin "1") (pinfunction "1_1") (pintype "bidirectional"))
      (node (ref "C46") (pin "1") (pinfunction "1_1") (pintype "bidirectional"))
      (node (ref "C47") (pin "1") (pinfunction "1_1") (pintype "bidirectional"))
      (node (ref "C48") (pin "1") (pinfunction "1_1") (pintype "bidirectional"))
      (node (ref "C49") (pin "1") (pinfunction "1_1") (pintype "bidirectional"))
      (node (ref "C5") (pin "1") (pinfunction "1_1") (pintype "bidirectional"))
      (node (ref "C50") (pin "1") (pinfunction "1_1") (pintype "bidirectional"))
      (node (ref "C51") (pin "1") (pinfunction "1_1") (pintype "bidirectional"))
      (node (ref "C52") (pin "1") (pinfunction "1_1") (pintype "bidirectional"))
      (node (ref "C55") (pin "1") (pinfunction "1_1") (pintype "bidirectional"))
      (node (ref "C57") (pin "1") (pinfunction "1_1") (pintype "bidirectional"))
      (node (ref "C59") (pin "1") (pinfunction "1_1") (pintype "bidirectional"))
      (node (ref "C61") (pin "1") (pinfunction "1_1") (pintype "bidirectional"))
      (node (ref "C62") (pin "2") (pinfunction "2_2") (pintype "bidirectional"))
      (node (ref "C64") (pin "1") (pinfunction "1_1") (pintype "bidirectional"))
      (node (ref "C65") (pin "1") (pinfunction "1_1") (pintype "bidirectional"))
      (node (ref "C66") (pin "1") (pinfunction "1_1") (pintype "bidirectional"))
      (node (ref "C69") (pin "1") (pinfunction "1_1") (pintype "bidirectional"))
      (node (ref "C71") (pin "1") (pinfunction "1_1") (pintype "bidirectional"))
      (node (ref "D2") (pin "1") (pinfunction "VDD_1") (pintype "bidirectional"))
      (node (ref "D3") (pin "1") (pinfunction "VDD_1") (pintype "bidirectional"))
      (node (ref "J4") (pin "1") (pinfunction "VCC_1") (pintype "bidirectional"))
      (node (ref "J5") (pin "1") (pinfunction "VCC_1") (pintype "bidirectional"))
      (node (ref "JP1") (pin "1") (pinfunction "1_1") (pintype "passive"))
      (node (ref "TP15") (pin "TP") (pinfunction "TP_TP") (pintype "input"))
      (node (ref "U1") (pin "15") (pinfunction "VDDLNA_15") (pintype "power_in"))
      (node (ref "U1") (pin "18") (pinfunction "VDDPA1_18") (pintype "power_in"))
      (node (ref "U1") (pin "19") (pinfunction "VDDPA2_19") (pintype "power_in"))
      (node (ref "U1") (pin "25") (pinfunction "VDDAON_25") (pintype "power_in"))
      (node (ref "U1") (pin "28") (pinfunction "VDDIOA_28") (pintype "power_in"))
      (node (ref "U1") (pin "47") (pinfunction "VDDBAT_47") (pintype "power_in"))
      (node (ref "U10") (pin "1") (pinfunction "VBAT_1") (pintype "power_in"))
      (node (ref "U10") (pin "24") (pinfunction "VDD/24_24") (pintype "power_in"))
      (node (ref "U10") (pin "36") (pinfunction "VDDIO2_36") (pintype "power_in"))
      (node (ref "U10") (pin "48") (pinfunction "VDD/48_48") (pintype "power_in"))
      (node (ref "U10") (pin "9") (pinfunction "VDDA_9") (pintype "power_in"))
      (node (ref "U3") (pin "10") (pinfunction "VDD_IO_10") (pintype "bidirectional"))
      (node (ref "U3") (pin "9") (pinfunction "VCC_9") (pintype "bidirectional"))
      (node (ref "U4") (pin "1") (pinfunction "VIN_1") (pintype "power_in"))
      (node (ref "U5") (pin "5") (pinfunction "OUT_5") (pintype "bidirectional"))
      (node (ref "U7") (pin "A22") (pinfunction "VDD_A22") (pintype "bidirectional"))
      (node (ref "U7") (pin "AD14") (pinfunction "VDD_AD14") (pintype "bidirectional"))
      (node (ref "U7") (pin "AD23") (pinfunction "VDD_AD23") (pintype "bidirectional"))
      (node (ref "U7") (pin "B1") (pinfunction "VDD_B1") (pintype "bidirectional"))
      (node (ref "U7") (pin "W1") (pinfunction "VDD_W1") (pintype "bidirectional"))
      (node (ref "U7") (pin "Y2") (pinfunction "VDDH_Y2") (pintype "bidirectional"))
      (node (ref "U8") (pin "5") (pinfunction "VSUPP_5") (pintype "bidirectional"))
      (node (ref "U8") (pin "6") (pinfunction "VSUPP_6") (pintype "bidirectional"))
    )
    (net (code "3") (name "ANT_SEL1") (class "Default")
      (node (ref "U10") (pin "27") (pinfunction "PB14_27") (pintype "bidirectional"))
      (node (ref "U9") (pin "3") (pinfunction "V1_3") (pintype "bidirectional"))
    )
    (net (code "4") (name "ANT_SEL2") (class "Default")
      (node (ref "U10") (pin "26") (pinfunction "PB13_26") (pintype "bidirectional"))
      (node (ref "U9") (pin "6") (pinfunction "V2_6") (pintype "bidirectional"))
    )
    (net (code "5") (name "ANT_SEL3") (class "Default")
      (node (ref "U10") (pin "25") (pinfunction "PB12_25") (pintype "bidirectional"))
      (node (ref "U9") (pin "7") (pinfunction "V3_7") (pintype "bidirectional"))
    )
    (net (code "6") (name "BATIN") (class "Default")
      (node (ref "C27") (pin "2") (pinfunction "2_2") (pintype "bidirectional"))
      (node (ref "R21") (pin "2") (pinfunction "2_2") (pintype "passive"))
      (node (ref "R22") (pin "1") (pinfunction "1_1") (pintype "passive"))
      (node (ref "U7") (pin "B9") (pinfunction "P0.30/AIN6_B9") (pintype "bidirectional"))
    )
    (net (code "7") (name "D+") (class "Default")
      (node (ref "J1") (pin "3") (pinfunction "D+_3") (pintype "bidirectional"))
      (node (ref "U2") (pin "14") (pinfunction "USBDP_14") (pintype "bidirectional"))
    )
    (net (code "8") (name "D-") (class "Default")
      (node (ref "J1") (pin "2") (pinfunction "D-_2") (pintype "bidirectional"))
      (node (ref "U2") (pin "15") (pinfunction "USBDM_15") (pintype "bidirectional"))
    )
    (net (code "9") (name "DBG_RX") (class "Default")
      (node (ref "R1") (pin "2") (pinfunction "2_2") (pintype "passive"))
      (node (ref "U7") (pin "M2") (pinfunction "P0.07_M2") (pintype "bidirectional"))
    )
    (net (code "10") (name "DBG_TX") (class "Default")
      (node (ref "R2") (pin "2") (pinfunction "2_2") (pintype "passive"))
      (node (ref "U7") (pin "T2") (pinfunction "P0.11_T2") (pintype "bidirectional"))
    )
    (net (code "11") (name "DW_IRQ") (class "Default")
      (node (ref "R20") (pin "2") (pinfunction "2_2") (pintype "passive"))
      (node (ref "U1") (pin "45") (pinfunction "IRQ/GPIO8_45") (pintype "bidirectional"))
      (node (ref "U10") (pin "20") (pinfunction "PB2_20") (pintype "bidirectional"))
    )
    (net (code "12") (name "DW_SPI_CLK") (class "Default")
      (node (ref "SPI_CLK") (pin "TP") (pinfunction "TP_TP") (pintype "input"))
      (node (ref "U1") (pin "41") (pinfunction "SPICLK_41") (pintype "input"))
      (node (ref "U10") (pin "15") (pinfunction "PA5_15") (pintype "bidirectional"))
    )
    (net (code "13") (name "DW_SPI_MISO") (class "Default")
      (node (ref "MISO") (pin "TP") (pinfunction "TP_TP") (pintype "input"))
      (node (ref "U1") (pin "40") (pinfunction "SPIMISO_40") (pintype "output"))
      (node (ref "U10") (pin "16") (pinfunction "PA6_16") (pintype "bidirectional"))
    )
    (net (code "14") (name "DW_SPI_MOSI") (class "Default")
      (node (ref "MOSI") (pin "TP") (pinfunction "TP_TP") (pintype "input"))
      (node (ref "U1") (pin "39") (pinfunction "SPIMOSI_39") (pintype "input"))
      (node (ref "U10") (pin "17") (pinfunction "PA7_17") (pintype "bidirectional"))
    )
    (net (code "15") (name "DW_SYNC") (class "Default")
      (node (ref "U1") (pin "29") (pinfunction "SYNC/GPIO7_29") (pintype "bidirectional"))
    )
    (net (code "16") (name "DW_WAKEUP") (class "Default")
      (node (ref "U1") (pin "23") (pinfunction "WAKEUP_23") (pintype "input"))
      (node (ref "U10") (pin "19") (pinfunction "PB1_19") (pintype "bidirectional"))
    )
    (net (code "17") (name "EXT_I2C_SCL") (class "Default")
      (node (ref "TP1") (pin "TP") (pinfunction "TP_TP") (pintype "input"))
      (node (ref "U10") (pin "30") (pinfunction "PA9_30") (pintype "bidirectional"))
      (node (ref "U7") (pin "R1") (pinfunction "P1.09_R1") (pintype "bidirectional"))
    )
    (net (code "18") (name "EXT_I2C_SDA") (class "Default")
      (node (ref "TP2") (pin "TP") (pinfunction "TP_TP") (pintype "input"))
      (node (ref "U10") (pin "31") (pinfunction "PA10_31") (pintype "bidirectional"))
      (node (ref "U7") (pin "U1") (pinfunction "P0.12_U1") (pintype "bidirectional"))
    )
    (net (code "19") (name "GND") (class "Default")
      (node (ref "A4") (pin "S2") (pinfunction "GND_S2") (pintype "bidirectional"))
      (node (ref "C1") (pin "2") (pinfunction "2_2") (pintype "bidirectional"))
      (node (ref "C10") (pin "1") (pinfunction "1_1") (pintype "bidirectional"))
      (node (ref "C11") (pin "1") (pinfunction "1_1") (pintype "bidirectional"))
      (node (ref "C12") (pin "2") (pinfunction "2_2") (pintype "bidirectional"))
      (node (ref "C13") (pin "2") (pinfunction "2_2") (pintype "bidirectional"))
      (node (ref "C14") (pin "2") (pinfunction "2_2") (pintype "bidirectional"))
      (node (ref "C15") (pin "2") (pinfunction "2_2") (pintype "bidirectional"))
      (node (ref "C18") (pin "2") (pinfunction "2_2") (pintype "bidirectional"))
      (node (ref "C19") (pin "2") (pinfunction "2_2") (pintype "bidirectional"))
      (node (ref "C2") (pin "2") (pinfunction "2_2") (pintype "bidirectional"))
      (node (ref "C20") (pin "2") (pinfunction "2_2") (pintype "bidirectional"))
      (node (ref "C21") (pin "2") (pinfunction "2_2") (pintype "bidirectional"))
      (node (ref "C23") (pin "2") (pinfunction "2_2") (pintype "bidirectional"))
      (node (ref "C24") (pin "2") (pinfunction "2_2") (pintype "bidirectional"))
      (node (ref "C25") (pin "2") (pinfunction "2_2") (pintype "bidirectional"))
      (node (ref "C26") (pin "2") (pinfunction "2_2") (pintype "bidirectional"))
      (node (ref "C27") (pin "1") (pinfunction "1_1") (pintype "bidirectional"))
      (node (ref "C28") (pin "2") (pinfunction "2_2") (pintype "bidirectional"))
      (node (ref "C29") (pin "2") (pinfunction "2_2") (pintype "bidirectional"))
      (node (ref "C30") (pin "2") (pinfunction "2_2") (pintype "bidirectional"))
      (node (ref "C31") (pin "2") (pinfunction "2_2") (pintype "bidirectional"))
      (node (ref "C32") (pin "2") (pinfunction "2_2") (pintype "bidirectional"))
      (node (ref "C33") (pin "2") (pinfunction "2_2") (pintype "bidirectional"))
      (node (ref "C34") (pin "2") (pinfunction "2_2") (pintype "bidirectional"))
      (node (ref "C35") (pin "2") (pinfunction "2_2") (pintype "bidirectional"))
      (node (ref "C36") (pin "2") (pinfunction "2_2") (pintype "bidirectional"))
      (node (ref "C37") (pin "2") (pinfunction "2_2") (pintype "bidirectional"))
      (node (ref "C38") (pin "2") (pinfunction "2_2") (pintype "bidirectional"))
      (node (ref "C39") (pin "2") (pinfunction "2_2") (pintype "bidirectional"))
      (node (ref "C4") (pin "2") (pinfunction "2_2") (pintype "bidirectional"))
      (node (ref "C40") (pin "2") (pinfunction "2_2") (pintype "bidirectional"))
      (node (ref "C41") (pin "2") (pinfunction "2_2") (pintype "bidirectional"))
      (node (ref "C42") (pin "2") (pinfunction "2_2") (pintype "bidirectional"))
      (node (ref "C43") (pin "2") (pinfunction "2_2") (pintype "bidirectional"))
      (node (ref "C44") (pin "2") (pinfunction "2_2") (pintype "bidirectional"))
      (node (ref "C45") (pin "2") (pinfunction "2_2") (pintype "bidirectional"))
      (node (ref "C46") (pin "2") (pinfunction "2_2") (pintype "bidirectional"))
      (node (ref "C47") (pin "2") (pinfunction "2_2") (pintype "bidirectional"))
      (node (ref "C48") (pin "2") (pinfunction "2_2") (pintype "bidirectional"))
      (node (ref "C49") (pin "2") (pinfunction "2_2") (pintype "bidirectional"))
      (node (ref "C5") (pin "2") (pinfunction "2_2") (pintype "bidirectional"))
      (node (ref "C50") (pin "2") (pinfunction "2_2") (pintype "bidirectional"))
      (node (ref "C51") (pin "2") (pinfunction "2_2") (pintype "bidirectional"))
      (node (ref "C52") (pin "2") (pinfunction "2_2") (pintype "bidirectional"))
      (node (ref "C53") (pin "2") (pinfunction "2_2") (pintype "bidirectional"))
      (node (ref "C54") (pin "2") (pinfunction "2_2") (pintype "bidirectional"))
      (node (ref "C55") (pin "2") (pinfunction "2_2") (pintype "bidirectional"))
      (node (ref "C56") (pin "2") (pinfunction "2_2") (pintype "bidirectional"))
      (node (ref "C57") (pin "2") (pinfunction "2_2") (pintype "bidirectional"))
      (node (ref "C58") (pin "2") (pinfunction "2_2") (pintype "bidirectional"))
      (node (ref "C59") (pin "2") (pinfunction "2_2") (pintype "bidirectional"))
      (node (ref "C60") (pin "2") (pinfunction "2_2") (pintype "bidirectional"))
      (node (ref "C61") (pin "2") (pinfunction "2_2") (pintype "bidirectional"))
      (node (ref "C62") (pin "1") (pinfunction "1_1") (pintype "bidirectional"))
      (node (ref "C63") (pin "2") (pinfunction "2_2") (pintype "bidirectional"))
      (node (ref "C64") (pin "2") (pinfunction "2_2") (pintype "bidirectional"))
      (node (ref "C65") (pin "2") (pinfunction "2_2") (pintype "bidirectional"))
      (node (ref "C66") (pin "2") (pinfunction "2_2") (pintype "bidirectional"))
      (node (ref "C67") (pin "2") (pinfunction "2_2") (pintype "bidirectional"))
      (node (ref "C68") (pin "2") (pinfunction "2_2") (pintype "bidirectional"))
      (node (ref "C69") (pin "2") (pinfunction "2_2") (pintype "bidirectional"))
      (node (ref "C70") (pin "2") (pinfunction "2_2") (pintype "bidirectional"))
      (node (ref "C71") (pin "2") (pinfunction "2_2") (pintype "bidirectional"))
      (node (ref "C8") (pin "1") (pinfunction "1_1") (pintype "bidirectional"))
      (node (ref "C9") (pin "1") (pinfunction "1_1") (pintype "bidirectional"))
      (node (ref "J1") (pin "5") (pinfunction "GND_5") (pintype "bidirectional"))
      (node (ref "J2") (pin "6") (pinfunction "GND_6") (pintype "bidirectional"))
      (node (ref "J2") (pin "B") (pinfunction "B_B") (pintype "bidirectional"))
      (node (ref "J2") (pin "MOUNT0") (pinfunction "GND_MOUNT0") (pintype "bidirectional"))
      (node (ref "J2") (pin "MOUNT1") (pinfunction "GND_MOUNT1") (pintype "bidirectional"))
      (node (ref "J2") (pin "MOUNT2") (pinfunction "GND_MOUNT2") (pintype "bidirectional"))
      (node (ref "J2") (pin "MOUNT3") (pinfunction "GND_MOUNT3") (pintype "bidirectional"))
      (node (ref "J3") (pin "N") (pinfunction "-_N") (pintype "bidirectional"))
      (node (ref "J4") (pin "5") (pinfunction "GND_5") (pintype "bidirectional"))
      (node (ref "J5") (pin "5") (pinfunction "GND_5") (pintype "bidirectional"))
      (node (ref "R11") (pin "1") (pinfunction "1_1") (pintype "passive"))
      (node (ref "R15") (pin "1") (pinfunction "1_1") (pintype "passive"))
      (node (ref "R16") (pin "2") (pinfunction "2_2") (pintype "passive"))
      (node (ref "R18") (pin "2") (pinfunction "2_2") (pintype "passive"))
      (node (ref "R20") (pin "1") (pinfunction "1_1") (pintype "passive"))
      (node (ref "R21") (pin "1") (pinfunction "1_1") (pintype "passive"))
      (node (ref "T1") (pin "2") (pinfunction "GND_2") (pintype "power_in"))
      (node (ref "T1") (pin "5") (pinfunction "GND_5") (pintype "power_in"))
      (node (ref "TP10") (pin "P$1") (pinfunction "TESTPOINT_P$1") (pintype "bidirectional"))
      (node (ref "TP4") (pin "TP") (pinfunction "TP_TP") (pintype "input"))
      (node (ref "U1") (pin "22") (pinfunction "FORCEON_22") (pintype "input"))
      (node (ref "U1") (pin "32") (pinfunction "VSSIO/32_32") (pintype "bidirectional"))
      (node (ref "U1") (pin "43") (pinfunction "VSSIO/43_43") (pintype "bidirectional"))
      (node (ref "U1") (pin "46") (pinfunction "TESTMODE_46") (pintype "input"))
      (node (ref "U1") (pin "GND") (pinfunction "GND_GND") (pintype "power_in"))
      (node (ref "U10") (pin "23") (pinfunction "VSS/23_23") (pintype "power_in"))
      (node (ref "U10") (pin "35") (pinfunction "VSS/35_35") (pintype "power_in"))
      (node (ref "U10") (pin "47") (pinfunction "VSS/47_47") (pintype "power_in"))
      (node (ref "U10") (pin "8") (pinfunction "VSSA_8") (pintype "power_in"))
      (node (ref "U10") (pin "GND") (pinfunction "GND_GND") (pintype "power_in"))
      (node (ref "U2") (pin "17") (pinfunction "GND_17") (pintype "power_in"))
      (node (ref "U2") (pin "20") (pinfunction "GND_20") (pintype "power_in"))
      (node (ref "U2") (pin "24") (pinfunction "GND_24") (pintype "power_in"))
      (node (ref "U2") (pin "26") (pinfunction "TEST_26") (pintype "input"))
      (node (ref "U2") (pin "4") (pinfunction "GND_4") (pintype "power_in"))
      (node (ref "U3") (pin "5") (pinfunction "GND_5") (pintype "bidirectional"))
      (node (ref "U3") (pin "6") (pinfunction "GND_6") (pintype "bidirectional"))
      (node (ref "U3") (pin "7") (pinfunction "GND_7") (pintype "bidirectional"))
      (node (ref "U3") (pin "8") (pinfunction "GND_8") (pintype "bidirectional"))
      (node (ref "U4") (pin "4") (pinfunction "GND_4") (pintype "power_in"))
      (node (ref "U5") (pin "2") (pinfunction "GND_2") (pintype "bidirectional"))
      (node (ref "U6") (pin "6") (pinfunction "VSS_6") (pintype "power_in"))
      (node (ref "U6") (pin "GND") (pinfunction "GND_GND") (pintype "power_in"))
      (node (ref "U7") (pin "AD2") (pinfunction "VBUS_AD2") (pintype "bidirectional"))
      (node (ref "U7") (pin "B7") (pinfunction "VSS_B7") (pintype "bidirectional"))
      (node (ref "U7") (pin "F23") (pinfunction "VSS_PA_F23") (pintype "bidirectional"))
      (node (ref "U7") (pin "GND") (pinfunction "VSS_GND") (pintype "bidirectional"))
      (node (ref "U8") (pin "4") (pinfunction "GND_4") (pintype "bidirectional"))
      (node (ref "U9") (pin "GND") (pinfunction "GND_GND") (pintype "power_in"))
      (node (ref "X2") (pin "2") (pinfunction "GND_2") (pintype "bidirectional"))
      (node (ref "X2") (pin "4") (pinfunction "GND_4") (pintype "bidirectional"))
      (node (ref "X3") (pin "2") (pinfunction "GND_2") (pintype "bidirectional"))
      (node (ref "X3") (pin "4") (pinfunction "GND_4") (pintype "bidirectional"))
      (node (ref "X4") (pin "2") (pinfunction "GND_2") (pintype "bidirectional"))
      (node (ref "X4") (pin "4") (pinfunction "GND_4") (pintype "bidirectional"))
    )
    (net (code "20") (name "GPIO0") (class "Default")
      (node (ref "GPIO0") (pin "P$1") (pinfunction "TESTPOINT_P$1") (pintype "bidirectional"))
      (node (ref "U10") (pin "42") (pinfunction "PB6_42") (pintype "bidirectional"))
    )
    (net (code "21") (name "GPIO1") (class "Default")
      (node (ref "GPIO1") (pin "P$1") (pinfunction "TESTPOINT_P$1") (pintype "bidirectional"))
      (node (ref "U10") (pin "43") (pinfunction "PB7_43") (pintype "bidirectional"))
    )
    (net (code "22") (name "GPIO2") (class "Default")
      (node (ref "TP5") (pin "P$1") (pinfunction "TESTPOINT_P$1") (pintype "bidirectional"))
      (node (ref "U10") (pin "29") (pinfunction "PA8_29") (pintype "bidirectional"))
    )
    (net (code "23") (name "GPIO3") (class "Default")
      (node (ref "TP6") (pin "P$1") (pinfunction "TESTPOINT_P$1") (pintype "bidirectional"))
      (node (ref "U10") (pin "28") (pinfunction "PB15_28") (pintype "bidirectional"))
    )
    (net (code "24") (name "LED_BLUE") (class "Default")
      (node (ref "R10") (pin "2") (pinfunction "2_2") (pintype "passive"))
      (node (ref "U10") (pin "40") (pinfunction "PB4_40") (pintype "bidirectional"))
    )
    (net (code "25") (name "LED_GREEN") (class "Default")
      (node (ref "R9") (pin "2") (pinfunction "2_2") (pintype "passive"))
      (node (ref "U10") (pin "41") (pinfunction "PB5_41") (pintype "bidirectional"))
    )
    (net (code "26") (name "LED_NRF_BLUE") (class "Default")
      (node (ref "R6") (pin "2") (pinfunction "2_2") (pintype "passive"))
      (node (ref "U7") (pin "J1") (pinfunction "P0.04/AIN2_J1") (pintype "bidirectional"))
    )
    (net (code "27") (name "LED_NRF_GREEN") (class "Default")
      (node (ref "R5") (pin "2") (pinfunction "2_2") (pintype "passive"))
      (node (ref "U7") (pin "L1") (pinfunction "P0.06_L1") (pintype "bidirectional"))
    )
    (net (code "28") (name "LED_NRF_RED") (class "Default")
      (node (ref "R4") (pin "2") (pinfunction "2_2") (pintype "passive"))
      (node (ref "U7") (pin "K2") (pinfunction "P0.05/AIN3_K2") (pintype "bidirectional"))
    )
    (net (code "29") (name "LED_RED") (class "Default")
      (node (ref "R8") (pin "2") (pinfunction "2_2") (pintype "passive"))
      (node (ref "U10") (pin "39") (pinfunction "PB3_39") (pintype "bidirectional"))
    )
    (net (code "30") (name "NRF_GPIO_0") (class "Default")
      (node (ref "TP13") (pin "P$1") (pinfunction "TESTPOINT_P$1") (pintype "bidirectional"))
      (node (ref "U7") (pin "H2") (pinfunction "P0.27_H2") (pintype "bidirectional"))
    )
    (net (code "31") (name "NRF_GPIO_1") (class "Default")
      (node (ref "TP14") (pin "P$1") (pinfunction "TESTPOINT_P$1") (pintype "bidirectional"))
      (node (ref "U7") (pin "G1") (pinfunction "P0.26_G1") (pintype "bidirectional"))
    )
    (net (code "32") (name "NRF_IMU_INT1") (class "Default")
      (node (ref "U3") (pin "12") (pinfunction "INT1_12") (pintype "bidirectional"))
      (node (ref "U7") (pin "AD18") (pinfunction "P0.22_AD18") (pintype "bidirectional"))
    )
    (net (code "33") (name "NRF_IMU_INT2") (class "Default")
      (node (ref "U3") (pin "11") (pinfunction "INT2_11") (pintype "bidirectional"))
      (node (ref "U7") (pin "AD20") (pinfunction "P0.24_AD20") (pintype "bidirectional"))
    )
    (net (code "34") (name "NRF_MISO") (class "Default")
      (node (ref "J2") (pin "7") (pinfunction "DATA0/MISO_7") (pintype "bidirectional"))
      (node (ref "R14") (pin "1") (pinfunction "1_1") (pintype "passive"))
      (node (ref "U3") (pin "3") (pinfunction "MISO/SA0_3") (pintype "bidirectional"))
      (node (ref "U7") (pin "AD10") (pinfunction "P0.15_AD10") (pintype "bidirectional"))
    )
    (net (code "35") (name "NRF_MOSI") (class "Default")
      (node (ref "J2") (pin "3") (pinfunction "CMD/MOSI_3") (pintype "bidirectional"))
      (node (ref "R12") (pin "1") (pinfunction "1_1") (pintype "passive"))
      (node (ref "U3") (pin "4") (pinfunction "MOSI/SDA_4") (pintype "bidirectional"))
      (node (ref "U7") (pin "AD8") (pinfunction "P0.13_AD8") (pintype "bidirectional"))
    )
    (net (code "36") (name "NRF_SCK") (class "Default")
      (node (ref "J2") (pin "5") (pinfunction "CLK_5") (pintype "bidirectional"))
      (node (ref "U3") (pin "1") (pinfunction "SCL/SPC_1") (pintype "bidirectional"))
      (node (ref "U7") (pin "AD12") (pinfunction "P0.17_AD12") (pintype "bidirectional"))
    )
    (net (code "37") (name "NRF_SWDCLK") (class "Default")
      (node (ref "J4") (pin "4") (pinfunction "SWDCLK_4") (pintype "bidirectional"))
      (node (ref "U7") (pin "AA24") (pinfunction "SWDCLK_AA24") (pintype "bidirectional"))
    )
    (net (code "38") (name "NRF_SWDIO") (class "Default")
      (node (ref "J4") (pin "2") (pinfunction "SWDIO_2") (pintype "bidirectional"))
      (node (ref "U7") (pin "AC24") (pinfunction "SWDIO_AC24") (pintype "bidirectional"))
    )
    (net (code "39") (name "Net-(A4-ANTENNA)") (class "Default")
      (node (ref "A4") (pin "S1") (pinfunction "ANTENNA_S1") (pintype "bidirectional"))
      (node (ref "C2") (pin "1") (pinfunction "1_1") (pintype "bidirectional"))
      (node (ref "L1") (pin "1") (pinfunction "1_1") (pintype "bidirectional"))
    )
    (net (code "40") (name "Net-(C6-2)") (class "Default")
      (node (ref "C6") (pin "P$2") (pinfunction "2_P$2") (pintype "bidirectional"))
      (node (ref "T1") (pin "3") (pinfunction "BAL/3_3") (pintype "bidirectional"))
    )
    (net (code "41") (name "Net-(C7-2)") (class "Default")
      (node (ref "C7") (pin "P$2") (pinfunction "2_P$2") (pintype "bidirectional"))
      (node (ref "T1") (pin "4") (pinfunction "BAL/4_4") (pintype "bidirectional"))
    )
    (net (code "42") (name "Net-(C17-Pad1)") (class "Default")
      (node (ref "C17") (pin "1") (pinfunction "1_1") (pintype "bidirectional"))
      (node (ref "R17") (pin "2") (pinfunction "2_2") (pintype "passive"))
    )
    (net (code "43") (name "Net-(C22-Pad1)") (class "Default")
      (node (ref "C22") (pin "1") (pinfunction "1_1") (pintype "bidirectional"))
      (node (ref "R3") (pin "2") (pinfunction "2_2") (pintype "passive"))
    )
    (net (code "44") (name "Net-(D1-PadA)") (class "Default")
      (node (ref "D1") (pin "A") (pinfunction "A_A") (pintype "passive"))
      (node (ref "R7") (pin "1") (pinfunction "1_1") (pintype "passive"))
    )
    (net (code "45") (name "Net-(D2-B)") (class "Default")
      (node (ref "D2") (pin "3") (pinfunction "B_3") (pintype "output"))
      (node (ref "R6") (pin "1") (pinfunction "1_1") (pintype "passive"))
    )
    (net (code "46") (name "Net-(D2-G)") (class "Default")
      (node (ref "D2") (pin "4") (pinfunction "G_4") (pintype "output"))
      (node (ref "R5") (pin "1") (pinfunction "1_1") (pintype "passive"))
    )
    (net (code "47") (name "Net-(D2-R)") (class "Default")
      (node (ref "D2") (pin "2") (pinfunction "R_2") (pintype "output"))
      (node (ref "R4") (pin "1") (pinfunction "1_1") (pintype "passive"))
    )
    (net (code "48") (name "Net-(D3-B)") (class "Default")
      (node (ref "D3") (pin "3") (pinfunction "B_3") (pintype "output"))
      (node (ref "R10") (pin "1") (pinfunction "1_1") (pintype "passive"))
      (node (ref "TP9") (pin "P$1") (pinfunction "TESTPOINT_P$1") (pintype "bidirectional"))
    )
    (net (code "49") (name "Net-(D3-G)") (class "Default")
      (node (ref "D3") (pin "4") (pinfunction "G_4") (pintype "output"))
      (node (ref "R9") (pin "1") (pinfunction "1_1") (pintype "passive"))
      (node (ref "TP7") (pin "P$1") (pinfunction "TESTPOINT_P$1") (pintype "bidirectional"))
    )
    (net (code "50") (name "Net-(D3-R)") (class "Default")
      (node (ref "D3") (pin "2") (pinfunction "R_2") (pintype "output"))
      (node (ref "R8") (pin "1") (pinfunction "1_1") (pintype "passive"))
      (node (ref "TP8") (pin "P$1") (pinfunction "TESTPOINT_P$1") (pintype "bidirectional"))
    )
    (net (code "51") (name "Net-(J2-VCC)") (class "Default")
      (node (ref "C60") (pin "1") (pinfunction "1_1") (pintype "bidirectional"))
      (node (ref "J2") (pin "4") (pinfunction "VCC_4") (pintype "bidirectional"))
      (node (ref "R12") (pin "2") (pinfunction "2_2") (pintype "passive"))
      (node (ref "R13") (pin "2") (pinfunction "2_2") (pintype "passive"))
      (node (ref "R14") (pin "2") (pinfunction "2_2") (pintype "passive"))
      (node (ref "R19") (pin "2") (pinfunction "2_2") (pintype "passive"))
      (node (ref "U8") (pin "1") (pinfunction "VLOAD_1") (pintype "bidirectional"))
      (node (ref "U8") (pin "2") (pinfunction "VLOAD_2") (pintype "bidirectional"))
    )
    (net (code "52") (name "Net-(L2-Pad2)") (class "Default")
      (node (ref "L2") (pin "2") (pinfunction "2_2") (pintype "bidirectional"))
      (node (ref "L3") (pin "1") (pinfunction "1_1") (pintype "bidirectional"))
    )
    (net (code "53") (name "Net-(T1-UNB)") (class "Default")
      (node (ref "T1") (pin "1") (pinfunction "UNB_1") (pintype "bidirectional"))
      (node (ref "U9") (pin "1") (pinfunction "RFC_1") (pintype "bidirectional"))
    )
    (net (code "54") (name "Net-(TP11-TESTPOINT)") (class "Default")
      (node (ref "TP11") (pin "P$1") (pinfunction "TESTPOINT_P$1") (pintype "bidirectional"))
      (node (ref "U1") (pin "36") (pinfunction "GPIO2_36") (pintype "bidirectional"))
    )
    (net (code "55") (name "Net-(TP12-TESTPOINT)") (class "Default")
      (node (ref "TP12") (pin "P$1") (pinfunction "TESTPOINT_P$1") (pintype "bidirectional"))
      (node (ref "U1") (pin "35") (pinfunction "GPIO3_35") (pintype "bidirectional"))
    )
    (net (code "56") (name "Net-(U1-CLKTUNE)") (class "Default")
      (node (ref "C3") (pin "1") (pinfunction "1_1") (pintype "bidirectional"))
      (node (ref "R17") (pin "1") (pinfunction "1_1") (pintype "passive"))
      (node (ref "U1") (pin "8") (pinfunction "CLKTUNE_8") (pintype "bidirectional"))
    )
    (net (code "57") (name "Net-(U1-VCOTUNE)") (class "Default")
      (node (ref "C16") (pin "1") (pinfunction "1_1") (pintype "bidirectional"))
      (node (ref "R3") (pin "1") (pinfunction "1_1") (pintype "passive"))
      (node (ref "U1") (pin "12") (pinfunction "VCOTUNE_12") (pintype "bidirectional"))
    )
    (net (code "58") (name "Net-(U1-VREF)") (class "Default")
      (node (ref "R15") (pin "2") (pinfunction "2_2") (pintype "passive"))
      (node (ref "U1") (pin "5") (pinfunction "VREF_5") (pintype "bidirectional"))
    )
    (net (code "59") (name "Net-(U2-3V3OUT)") (class "Default")
      (node (ref "C28") (pin "1") (pinfunction "1_1") (pintype "bidirectional"))
      (node (ref "U2") (pin "1") (pinfunction "VCCIO_1") (pintype "power_in"))
      (node (ref "U2") (pin "16") (pinfunction "3V3OUT_16") (pintype "output"))
    )
    (net (code "60") (name "Net-(U2-RXD)") (class "Default")
      (node (ref "R2") (pin "1") (pinfunction "1_1") (pintype "passive"))
      (node (ref "U2") (pin "2") (pinfunction "RXD_2") (pintype "input"))
    )
    (net (code "61") (name "Net-(U2-TXD)") (class "Default")
      (node (ref "R1") (pin "1") (pinfunction "1_1") (pintype "passive"))
      (node (ref "U2") (pin "30") (pinfunction "TXD_30") (pintype "output"))
    )
    (net (code "62") (name "Net-(U5-BP)") (class "Default")
      (node (ref "C23") (pin "1") (pinfunction "1_1") (pintype "bidirectional"))
      (node (ref "U5") (pin "4") (pinfunction "BP_4") (pintype "bidirectional"))
    )
    (net (code "63") (name "Net-(U6-PROG)") (class "Default")
      (node (ref "R11") (pin "2") (pinfunction "2_2") (pintype "passive"))
      (node (ref "U6") (pin "8") (pinfunction "PROG_8") (pintype "bidirectional"))
    )
    (net (code "64") (name "Net-(U6-STAT)") (class "Default")
      (node (ref "D1") (pin "C") (pinfunction "C_C") (pintype "passive"))
      (node (ref "U6") (pin "5") (pinfunction "STAT_5") (pintype "bidirectional"))
    )
    (net (code "65") (name "Net-(U7-ANT)") (class "Default")
      (node (ref "C1") (pin "1") (pinfunction "1_1") (pintype "bidirectional"))
      (node (ref "L1") (pin "2") (pinfunction "2_2") (pintype "bidirectional"))
      (node (ref "U7") (pin "H23") (pinfunction "ANT_H23") (pintype "bidirectional"))
    )
    (net (code "66") (name "Net-(U7-DCC)") (class "Default")
      (node (ref "L3") (pin "2") (pinfunction "2_2") (pintype "bidirectional"))
      (node (ref "U7") (pin "B3") (pinfunction "DCC_B3") (pintype "bidirectional"))
    )
    (net (code "67") (name "Net-(U7-DEC1)") (class "Default")
      (node (ref "C32") (pin "1") (pinfunction "1_1") (pintype "bidirectional"))
      (node (ref "U7") (pin "C1") (pinfunction "DEC1_C1") (pintype "bidirectional"))
    )
    (net (code "68") (name "Net-(U7-DEC3)") (class "Default")
      (node (ref "C18") (pin "1") (pinfunction "1_1") (pintype "bidirectional"))
      (node (ref "U7") (pin "D23") (pinfunction "DEC3_D23") (pintype "bidirectional"))
    )
    (net (code "69") (name "Net-(U7-DEC4)") (class "Default")
      (node (ref "C26") (pin "1") (pinfunction "1_1") (pintype "bidirectional"))
      (node (ref "C56") (pin "1") (pinfunction "1_1") (pintype "bidirectional"))
      (node (ref "L2") (pin "1") (pinfunction "1_1") (pintype "bidirectional"))
      (node (ref "U7") (pin "B5") (pinfunction "DEC4_B5") (pintype "bidirectional"))
      (node (ref "U7") (pin "E24") (pinfunction "DEC6_E24") (pintype "bidirectional"))
    )
    (net (code "70") (name "Net-(U7-DEC5)") (class "Default")
      (node (ref "C21") (pin "1") (pinfunction "1_1") (pintype "bidirectional"))
      (node (ref "U7") (pin "N24") (pinfunction "DEC5_N24") (pintype "bidirectional"))
    )
    (net (code "71") (name "Net-(U7-XC1)") (class "Default")
      (node (ref "C8") (pin "2") (pinfunction "2_2") (pintype "bidirectional"))
      (node (ref "U7") (pin "B24") (pinfunction "XC1_B24") (pintype "bidirectional"))
      (node (ref "X3") (pin "3") (pinfunction "2_3") (pintype "bidirectional"))
    )
    (net (code "72") (name "Net-(U7-XC2)") (class "Default")
      (node (ref "C9") (pin "2") (pinfunction "2_2") (pintype "bidirectional"))
      (node (ref "U7") (pin "A23") (pinfunction "XC2_A23") (pintype "bidirectional"))
      (node (ref "X3") (pin "1") (pinfunction "1_1") (pintype "bidirectional"))
    )
    (net (code "73") (name "Net-(U10-PF11-BOOT0)") (class "Default")
      (node (ref "R16") (pin "1") (pinfunction "1_1") (pintype "passive"))
      (node (ref "U10") (pin "44") (pinfunction "PF11-BOOT0_44") (pintype "bidirectional"))
    )
    (net (code "74") (name "OSC_IN") (class "Default")
      (node (ref "C14") (pin "1") (pinfunction "1_1") (pintype "bidirectional"))
      (node (ref "U10") (pin "5") (pinfunction "PF0-OSC_IN_5") (pintype "bidirectional"))
      (node (ref "X2") (pin "1") (pinfunction "1_1") (pintype "bidirectional"))
    )
    (net (code "75") (name "OSC_OUT") (class "Default")
      (node (ref "C15") (pin "1") (pinfunction "1_1") (pintype "bidirectional"))
      (node (ref "U10") (pin "6") (pinfunction "PF1-OSC_OUT_6") (pintype "bidirectional"))
      (node (ref "X2") (pin "3") (pinfunction "2_3") (pintype "bidirectional"))
    )
    (net (code "76") (name "REG_EN") (class "Default")
      (node (ref "U1") (pin "21") (pinfunction "EXTON_21") (pintype "output"))
      (node (ref "U4") (pin "2") (pinfunction "EN_2") (pintype "bidirectional"))
    )
    (net (code "77") (name "RF1") (class "Default")
      (node (ref "A1") (pin "A") (pinfunction "ANTENNA_A") (pintype "bidirectional"))
      (node (ref "U9") (pin "4") (pinfunction "RF1_4") (pintype "bidirectional"))
    )
    (net (code "78") (name "RF2") (class "Default")
      (node (ref "A2") (pin "A") (pinfunction "ANTENNA_A") (pintype "bidirectional"))
      (node (ref "U9") (pin "5") (pinfunction "RF2_5") (pintype "bidirectional"))
    )
    (net (code "79") (name "RF3") (class "Default")
      (node (ref "A3") (pin "A") (pinfunction "ANTENNA_A") (pintype "bidirectional"))
      (node (ref "U9") (pin "8") (pinfunction "RF3_8") (pintype "bidirectional"))
    )
    (net (code "80") (name "RF_N") (class "Default")
      (node (ref "C6") (pin "P$1") (pinfunction "1_P$1") (pintype "bidirectional"))
      (node (ref "U1") (pin "17") (pinfunction "RF_N_17") (pintype "bidirectional"))
    )
    (net (code "81") (name "RF_P") (class "Default")
      (node (ref "C7") (pin "P$1") (pinfunction "1_P$1") (pintype "bidirectional"))
      (node (ref "U1") (pin "16") (pinfunction "RF_P_16") (pintype "bidirectional"))
    )
    (net (code "82") (name "SD_EN") (class "Default")
      (node (ref "R18") (pin "1") (pinfunction "1_1") (pintype "passive"))
      (node (ref "U7") (pin "AC9") (pinfunction "P0.14_AC9") (pintype "bidirectional"))
      (node (ref "U8") (pin "3") (pinfunction "EN_3") (pintype "bidirectional"))
    )
    (net (code "83") (name "STM_INTERRUPT") (class "Default")
      (node (ref "TP3") (pin "TP") (pinfunction "TP_TP") (pintype "input"))
      (node (ref "U10") (pin "12") (pinfunction "PA2_12") (pintype "bidirectional"))
      (node (ref "U7") (pin "N1") (pinfunction "P0.08_N1") (pintype "bidirectional"))
    )
    (net (code "84") (name "STM_SWCLK") (class "Default")
      (node (ref "J5") (pin "4") (pinfunction "SWDCLK_4") (pintype "bidirectional"))
      (node (ref "U10") (pin "37") (pinfunction "PA14_37") (pintype "bidirectional"))
    )
    (net (code "85") (name "STM_SWDIO") (class "Default")
      (node (ref "J5") (pin "2") (pinfunction "SWDIO_2") (pintype "bidirectional"))
      (node (ref "U10") (pin "34") (pinfunction "PA13_34") (pintype "bidirectional"))
    )
    (net (code "86") (name "VBAT") (class "Default")
      (node (ref "C58") (pin "1") (pinfunction "1_1") (pintype "bidirectional"))
      (node (ref "C68") (pin "1") (pinfunction "1_1") (pintype "bidirectional"))
      (node (ref "J3") (pin "P") (pinfunction "+_P") (pintype "bidirectional"))
      (node (ref "R22") (pin "2") (pinfunction "2_2") (pintype "passive"))
      (node (ref "U5") (pin "1") (pinfunction "IN_1") (pintype "bidirectional"))
      (node (ref "U5") (pin "3") (pinfunction "~{SHDN}_3") (pintype "bidirectional"))
      (node (ref "U6") (pin "3") (pinfunction "VBAT/3_3") (pintype "power_in"))
      (node (ref "U6") (pin "4") (pinfunction "VBAT/4_4") (pintype "power_in"))
    )
    (net (code "87") (name "VDDCLK") (class "Default")
      (node (ref "C17") (pin "2") (pinfunction "2_2") (pintype "bidirectional"))
      (node (ref "C3") (pin "2") (pinfunction "2_2") (pintype "bidirectional"))
      (node (ref "C39") (pin "1") (pinfunction "1_1") (pintype "bidirectional"))
      (node (ref "U1") (pin "9") (pinfunction "VDDCLK_9") (pintype "power_in"))
    )
    (net (code "88") (name "VDDDIG") (class "Default")
      (node (ref "C35") (pin "1") (pinfunction "1_1") (pintype "bidirectional"))
      (node (ref "C36") (pin "1") (pinfunction "1_1") (pintype "bidirectional"))
      (node (ref "U1") (pin "20") (pinfunction "VDDREG_20") (pintype "power_in"))
      (node (ref "U1") (pin "44") (pinfunction "VDDDIG_44") (pintype "power_in"))
    )
    (net (code "89") (name "VDDIF") (class "Default")
      (node (ref "C42") (pin "1") (pinfunction "1_1") (pintype "bidirectional"))
      (node (ref "U1") (pin "7") (pinfunction "VDDIF_7") (pintype "power_in"))
    )
    (net (code "90") (name "VDDIO") (class "Default")
      (node (ref "C41") (pin "1") (pinfunction "1_1") (pintype "bidirectional"))
      (node (ref "C53") (pin "1") (pinfunction "1_1") (pintype "bidirectional"))
      (node (ref "U1") (pin "31") (pinfunction "VDDIO/31_31") (pintype "power_in"))
      (node (ref "U1") (pin "42") (pinfunction "VDDIO/42_42") (pintype "power_in"))
    )
    (net (code "91") (name "VDDMS") (class "Default")
      (node (ref "C38") (pin "1") (pinfunction "1_1") (pintype "bidirectional"))
      (node (ref "U1") (pin "6") (pinfunction "VDDMS_6") (pintype "power_in"))
    )
    (net (code "92") (name "VDDSYN") (class "Default")
      (node (ref "C40") (pin "1") (pinfunction "1_1") (pintype "bidirectional"))
      (node (ref "U1") (pin "10") (pinfunction "VDDSYN_10") (pintype "power_in"))
    )
    (net (code "93") (name "VDDVCO") (class "Default")
      (node (ref "C16") (pin "2") (pinfunction "2_2") (pintype "bidirectional"))
      (node (ref "C22") (pin "2") (pinfunction "2_2") (pintype "bidirectional"))
      (node (ref "C43") (pin "1") (pinfunction "1_1") (pintype "bidirectional"))
      (node (ref "U1") (pin "11") (pinfunction "VDDVCO_11") (pintype "power_in"))
    )
    (net (code "94") (name "VUSB") (class "Default")
      (node (ref "C54") (pin "1") (pinfunction "1_1") (pintype "bidirectional"))
      (node (ref "C67") (pin "1") (pinfunction "1_1") (pintype "bidirectional"))
      (node (ref "J1") (pin "1") (pinfunction "+5V_1") (pintype "bidirectional"))
      (node (ref "R7") (pin "2") (pinfunction "2_2") (pintype "passive"))
      (node (ref "U2") (pin "19") (pinfunction "VCC_19") (pintype "power_in"))
      (node (ref "U6") (pin "1") (pinfunction "VDD/1_1") (pintype "power_in"))
      (node (ref "U6") (pin "2") (pinfunction "VDD/2_2") (pintype "power_in"))
    )
    (net (code "95") (name "XL3") (class "Default")
      (node (ref "C11") (pin "2") (pinfunction "2_2") (pintype "bidirectional"))
      (node (ref "U7") (pin "D2") (pinfunction "P0.00/XL1_D2") (pintype "bidirectional"))
      (node (ref "X1") (pin "A") (pinfunction "1_A") (pintype "bidirectional"))
    )
    (net (code "96") (name "XL4") (class "Default")
      (node (ref "C10") (pin "2") (pinfunction "2_2") (pintype "bidirectional"))
      (node (ref "U7") (pin "F2") (pinfunction "P0.01/XL2_F2") (pintype "bidirectional"))
      (node (ref "X1") (pin "B") (pinfunction "2_B") (pintype "bidirectional"))
    )
    (net (code "97") (name "XTAL1") (class "Default")
      (node (ref "C13") (pin "1") (pinfunction "1_1") (pintype "bidirectional"))
      (node (ref "U1") (pin "3") (pinfunction "XTAL1_3") (pintype "input"))
      (node (ref "X4") (pin "3") (pinfunction "2_3") (pintype "bidirectional"))
    )
    (net (code "98") (name "XTAL2") (class "Default")
      (node (ref "C12") (pin "1") (pinfunction "1_1") (pintype "bidirectional"))
      (node (ref "U1") (pin "4") (pinfunction "XTAL2_4") (pintype "input"))
      (node (ref "X4") (pin "1") (pinfunction "1_1") (pintype "bidirectional"))
    )
    (net (code "99") (name "unconnected-(J1-ID-Pad4)") (class "Default")
      (node (ref "J1") (pin "4") (pinfunction "ID_4") (pintype "bidirectional"))
    )
    (net (code "100") (name "unconnected-(J2-DATA1{slash}RSV-Pad8)") (class "Default")
      (node (ref "J2") (pin "8") (pinfunction "DATA1/RSV_8") (pintype "bidirectional"))
    )
    (net (code "101") (name "unconnected-(J2-DATA2{slash}NC-Pad1)") (class "Default")
      (node (ref "J2") (pin "1") (pinfunction "DATA2/NC_1") (pintype "bidirectional"))
    )
    (net (code "102") (name "unconnected-(J4-SWO-Pad6)") (class "Default")
      (node (ref "J4") (pin "6") (pinfunction "SWO_6") (pintype "bidirectional"))
    )
    (net (code "103") (name "unconnected-(J5-SWO-Pad6)") (class "Default")
      (node (ref "J5") (pin "6") (pinfunction "SWO_6") (pintype "bidirectional"))
    )
    (net (code "104") (name "unconnected-(U1-GPIO0-Pad38)") (class "Default")
      (node (ref "U1") (pin "38") (pinfunction "GPIO0_38") (pintype "bidirectional"))
    )
    (net (code "105") (name "unconnected-(U1-GPIO1-Pad37)") (class "Default")
      (node (ref "U1") (pin "37") (pinfunction "GPIO1_37") (pintype "bidirectional"))
    )
    (net (code "106") (name "unconnected-(U1-GPIO4-Pad34)") (class "Default")
      (node (ref "U1") (pin "34") (pinfunction "GPIO4_34") (pintype "bidirectional"))
    )
    (net (code "107") (name "unconnected-(U1-GPIO5-Pad33)") (class "Default")
      (node (ref "U1") (pin "33") (pinfunction "GPIO5_33") (pintype "bidirectional"))
    )
    (net (code "108") (name "unconnected-(U1-GPIO6-Pad30)") (class "Default")
      (node (ref "U1") (pin "30") (pinfunction "GPIO6_30") (pintype "bidirectional"))
    )
    (net (code "109") (name "unconnected-(U2-CBUS0-Pad22)") (class "Default")
      (node (ref "U2") (pin "22") (pinfunction "CBUS0_22") (pintype "bidirectional"))
    )
    (net (code "110") (name "unconnected-(U2-CBUS1-Pad21)") (class "Default")
      (node (ref "U2") (pin "21") (pinfunction "CBUS1_21") (pintype "bidirectional"))
    )
    (net (code "111") (name "unconnected-(U2-CBUS2-Pad10)") (class "Default")
      (node (ref "U2") (pin "10") (pinfunction "CBUS2_10") (pintype "bidirectional"))
    )
    (net (code "112") (name "unconnected-(U2-CBUS3-Pad11)") (class "Default")
      (node (ref "U2") (pin "11") (pinfunction "CBUS3_11") (pintype "bidirectional"))
    )
    (net (code "113") (name "unconnected-(U2-CBUS4-Pad9)") (class "Default")
      (node (ref "U2") (pin "9") (pinfunction "CBUS4_9") (pintype "bidirectional"))
    )
    (net (code "114") (name "unconnected-(U2-OSCI-Pad27)") (class "Default")
      (node (ref "U2") (pin "27") (pinfunction "OSCI_27") (pintype "input"))
    )
    (net (code "115") (name "unconnected-(U2-OSCO-Pad28)") (class "Default")
      (node (ref "U2") (pin "28") (pinfunction "OSCO_28") (pintype "output"))
    )
    (net (code "116") (name "unconnected-(U2-~{CTS}-Pad8)") (class "Default")
      (node (ref "U2") (pin "8") (pinfunction "~{CTS}_8") (pintype "input"))
    )
    (net (code "117") (name "unconnected-(U2-~{DCD}-Pad7)") (class "Default")
      (node (ref "U2") (pin "7") (pinfunction "~{DCD}_7") (pintype "input"))
    )
    (net (code "118") (name "unconnected-(U2-~{DSR}-Pad6)") (class "Default")
      (node (ref "U2") (pin "6") (pinfunction "~{DSR}_6") (pintype "input"))
    )
    (net (code "119") (name "unconnected-(U2-~{DTR}-Pad31)") (class "Default")
      (node (ref "U2") (pin "31") (pinfunction "~{DTR}_31") (pintype "output"))
    )
    (net (code "120") (name "unconnected-(U2-~{RI}-Pad3)") (class "Default")
      (node (ref "U2") (pin "3") (pinfunction "~{RI}_3") (pintype "input"))
    )
    (net (code "121") (name "unconnected-(U2-~{RTS}-Pad32)") (class "Default")
      (node (ref "U2") (pin "32") (pinfunction "~{RTS}_32") (pintype "output"))
    )
    (net (code "122") (name "unconnected-(U6-NC-Pad7)") (class "Default")
      (node (ref "U6") (pin "7") (pinfunction "NC_7") (pintype "no_connect"))
    )
    (net (code "123") (name "unconnected-(U7-D+-PadAD6)") (class "Default")
      (node (ref "U7") (pin "AD6") (pinfunction "D+_AD6") (pintype "bidirectional"))
    )
    (net (code "124") (name "unconnected-(U7-D--PadAD4)") (class "Default")
      (node (ref "U7") (pin "AD4") (pinfunction "D-_AD4") (pintype "bidirectional"))
    )
    (net (code "125") (name "unconnected-(U7-DCCH-PadAB2)") (class "Default")
      (node (ref "U7") (pin "AB2") (pinfunction "DCCH_AB2") (pintype "bidirectional"))
    )
    (net (code "126") (name "unconnected-(U7-DEC2-PadA18)") (class "Default")
      (node (ref "U7") (pin "A18") (pinfunction "DEC2_A18") (pintype "bidirectional"))
    )
    (net (code "127") (name "unconnected-(U7-DECUSB-PadAC5)") (class "Default")
      (node (ref "U7") (pin "AC5") (pinfunction "DECUSB_AC5") (pintype "bidirectional"))
    )
    (net (code "128") (name "unconnected-(U7-P0.02{slash}AIN0-PadA12)") (class "Default")
      (node (ref "U7") (pin "A12") (pinfunction "P0.02/AIN0_A12") (pintype "bidirectional"))
    )
    (net (code "129") (name "unconnected-(U7-P0.03{slash}AIN1-PadB13)") (class "Default")
      (node (ref "U7") (pin "B13") (pinfunction "P0.03/AIN1_B13") (pintype "bidirectional"))
    )
    (net (code "130") (name "unconnected-(U7-P0.09{slash}NFC1-PadL24)") (class "Default")
      (node (ref "U7") (pin "L24") (pinfunction "P0.09/NFC1_L24") (pintype "bidirectional"))
    )
    (net (code "131") (name "unconnected-(U7-P0.10{slash}NFC2-PadJ24)") (class "Default")
      (node (ref "U7") (pin "J24") (pinfunction "P0.10/NFC2_J24") (pintype "bidirectional"))
    )
    (net (code "132") (name "unconnected-(U7-P0.19-PadAC15)") (class "Default")
      (node (ref "U7") (pin "AC15") (pinfunction "P0.19_AC15") (pintype "bidirectional"))
    )
    (net (code "133") (name "unconnected-(U7-P0.21-PadAC17)") (class "Default")
      (node (ref "U7") (pin "AC17") (pinfunction "P0.21_AC17") (pintype "bidirectional"))
    )
    (net (code "134") (name "unconnected-(U7-P0.23-PadAC19)") (class "Default")
      (node (ref "U7") (pin "AC19") (pinfunction "P0.23_AC19") (pintype "bidirectional"))
    )
    (net (code "135") (name "unconnected-(U7-P0.25-PadAC21)") (class "Default")
      (node (ref "U7") (pin "AC21") (pinfunction "P0.25_AC21") (pintype "bidirectional"))
    )
    (net (code "136") (name "unconnected-(U7-P0.28{slash}AIN4-PadB11)") (class "Default")
      (node (ref "U7") (pin "B11") (pinfunction "P0.28/AIN4_B11") (pintype "bidirectional"))
    )
    (net (code "137") (name "unconnected-(U7-P0.29{slash}AIN5-PadA10)") (class "Default")
      (node (ref "U7") (pin "A10") (pinfunction "P0.29/AIN5_A10") (pintype "bidirectional"))
    )
    (net (code "138") (name "unconnected-(U7-P0.31{slash}AIN7-PadA8)") (class "Default")
      (node (ref "U7") (pin "A8") (pinfunction "P0.31/AIN7_A8") (pintype "bidirectional"))
    )
    (net (code "139") (name "unconnected-(U7-P1.01-PadY23)") (class "Default")
      (node (ref "U7") (pin "Y23") (pinfunction "P1.01_Y23") (pintype "bidirectional"))
    )
    (net (code "140") (name "unconnected-(U7-P1.02-PadW24)") (class "Default")
      (node (ref "U7") (pin "W24") (pinfunction "P1.02_W24") (pintype "bidirectional"))
    )
    (net (code "141") (name "unconnected-(U7-P1.03-PadV23)") (class "Default")
      (node (ref "U7") (pin "V23") (pinfunction "P1.03_V23") (pintype "bidirectional"))
    )
    (net (code "142") (name "unconnected-(U7-P1.04-PadU24)") (class "Default")
      (node (ref "U7") (pin "U24") (pinfunction "P1.04_U24") (pintype "bidirectional"))
    )
    (net (code "143") (name "unconnected-(U7-P1.05-PadT23)") (class "Default")
      (node (ref "U7") (pin "T23") (pinfunction "P1.05_T23") (pintype "bidirectional"))
    )
    (net (code "144") (name "unconnected-(U7-P1.06-PadR24)") (class "Default")
      (node (ref "U7") (pin "R24") (pinfunction "P1.06_R24") (pintype "bidirectional"))
    )
    (net (code "145") (name "unconnected-(U7-P1.07-PadP23)") (class "Default")
      (node (ref "U7") (pin "P23") (pinfunction "P1.07_P23") (pintype "bidirectional"))
    )
    (net (code "146") (name "unconnected-(U7-P1.10-PadA20)") (class "Default")
      (node (ref "U7") (pin "A20") (pinfunction "P1.10_A20") (pintype "bidirectional"))
    )
    (net (code "147") (name "unconnected-(U7-P1.11-PadB19)") (class "Default")
      (node (ref "U7") (pin "B19") (pinfunction "P1.11_B19") (pintype "bidirectional"))
    )
    (net (code "148") (name "unconnected-(U7-P1.12-PadB17)") (class "Default")
      (node (ref "U7") (pin "B17") (pinfunction "P1.12_B17") (pintype "bidirectional"))
    )
    (net (code "149") (name "unconnected-(U7-P1.13-PadA16)") (class "Default")
      (node (ref "U7") (pin "A16") (pinfunction "P1.13_A16") (pintype "bidirectional"))
    )
    (net (code "150") (name "unconnected-(U7-P1.14-PadB15)") (class "Default")
      (node (ref "U7") (pin "B15") (pinfunction "P1.14_B15") (pintype "bidirectional"))
    )
    (net (code "151") (name "unconnected-(U7-P1.15-PadA14)") (class "Default")
      (node (ref "U7") (pin "A14") (pinfunction "P1.15_A14") (pintype "bidirectional"))
    )
    (net (code "152") (name "unconnected-(U10-PA0-Pad10)") (class "Default")
      (node (ref "U10") (pin "10") (pinfunction "PA0_10") (pintype "bidirectional"))
    )
    (net (code "153") (name "unconnected-(U10-PA1-Pad11)") (class "Default")
      (node (ref "U10") (pin "11") (pinfunction "PA1_11") (pintype "bidirectional"))
    )
    (net (code "154") (name "unconnected-(U10-PA3-Pad13)") (class "Default")
      (node (ref "U10") (pin "13") (pinfunction "PA3_13") (pintype "bidirectional"))
    )
    (net (code "155") (name "unconnected-(U10-PA11-Pad32)") (class "Default")
      (node (ref "U10") (pin "32") (pinfunction "PA11_32") (pintype "bidirectional"))
    )
    (net (code "156") (name "unconnected-(U10-PA12-Pad33)") (class "Default")
      (node (ref "U10") (pin "33") (pinfunction "PA12_33") (pintype "bidirectional"))
    )
    (net (code "157") (name "unconnected-(U10-PA15-Pad38)") (class "Default")
      (node (ref "U10") (pin "38") (pinfunction "PA15_38") (pintype "bidirectional"))
    )
    (net (code "158") (name "unconnected-(U10-PB8-Pad45)") (class "Default")
      (node (ref "U10") (pin "45") (pinfunction "PB8_45") (pintype "bidirectional"))
    )
    (net (code "159") (name "unconnected-(U10-PB9-Pad46)") (class "Default")
      (node (ref "U10") (pin "46") (pinfunction "PB9_46") (pintype "bidirectional"))
    )
    (net (code "160") (name "unconnected-(U10-PB10-Pad21)") (class "Default")
      (node (ref "U10") (pin "21") (pinfunction "PB10_21") (pintype "bidirectional"))
    )
    (net (code "161") (name "unconnected-(U10-PB11-Pad22)") (class "Default")
      (node (ref "U10") (pin "22") (pinfunction "PB11_22") (pintype "bidirectional"))
    )
    (net (code "162") (name "unconnected-(U10-PC13-Pad2)") (class "Default")
      (node (ref "U10") (pin "2") (pinfunction "PC13_2") (pintype "bidirectional"))
    )
    (net (code "163") (name "unconnected-(U10-PC14-OSC32_IN-Pad3)") (class "Default")
      (node (ref "U10") (pin "3") (pinfunction "PC14-OSC32_IN_3") (pintype "bidirectional"))
    )
    (net (code "164") (name "unconnected-(U10-PC15-OSC32_OUT-Pad4)") (class "Default")
      (node (ref "U10") (pin "4") (pinfunction "PC15-OSC32_OUT_4") (pintype "bidirectional"))
    )
    (net (code "165") (name "~{DW_RST}") (class "Default")
      (node (ref "U1") (pin "27") (pinfunction "~{RST}_27") (pintype "bidirectional"))
      (node (ref "U10") (pin "18") (pinfunction "PB0_18") (pintype "bidirectional"))
    )
    (net (code "166") (name "~{DW_SPI_CS}") (class "Default")
      (node (ref "U1") (pin "24") (pinfunction "~{SPICS}_24") (pintype "input"))
      (node (ref "U10") (pin "14") (pinfunction "PA4_14") (pintype "bidirectional"))
    )
    (net (code "167") (name "~{FT_RST}") (class "Default")
      (node (ref "U2") (pin "18") (pinfunction "~{RESET}_18") (pintype "input"))
      (node (ref "U7") (pin "P2") (pinfunction "P1.08_P2") (pintype "bidirectional"))
    )
    (net (code "168") (name "~{NRF_CS_IMU}") (class "Default")
      (node (ref "U3") (pin "2") (pinfunction "CS_2") (pintype "bidirectional"))
      (node (ref "U7") (pin "AC11") (pinfunction "P0.16_AC11") (pintype "bidirectional"))
    )
    (net (code "169") (name "~{NRF_CS_SD}") (class "Default")
      (node (ref "J2") (pin "2") (pinfunction "DATA3-CD/CS_N_2") (pintype "bidirectional"))
      (node (ref "R13") (pin "1") (pinfunction "1_1") (pintype "passive"))
      (node (ref "U7") (pin "AD16") (pinfunction "P0.20_AD16") (pintype "bidirectional"))
    )
    (net (code "170") (name "~{NRF_RST}") (class "Default")
      (node (ref "J4") (pin "3") (pinfunction "~{RESET}_3") (pintype "bidirectional"))
      (node (ref "U7") (pin "AC13") (pinfunction "P0.18_AC13") (pintype "bidirectional"))
    )
    (net (code "171") (name "~{SD_DETECT}") (class "Default")
      (node (ref "J2") (pin "A") (pinfunction "A_A") (pintype "bidirectional"))
      (node (ref "R19") (pin "1") (pinfunction "1_1") (pintype "passive"))
      (node (ref "U7") (pin "AD22") (pinfunction "P1.00_AD22") (pintype "bidirectional"))
    )
    (net (code "172") (name "~{STM_RST}") (class "Default")
      (node (ref "J5") (pin "3") (pinfunction "~{RESET}_3") (pintype "bidirectional"))
      (node (ref "U10") (pin "7") (pinfunction "~{RST}_7") (pintype "bidirectional"))
    )
  )
)
